# Respeaker_Microphone_Array_v1_0.net
KiCad netlist of a schematic drawn in EAGLE
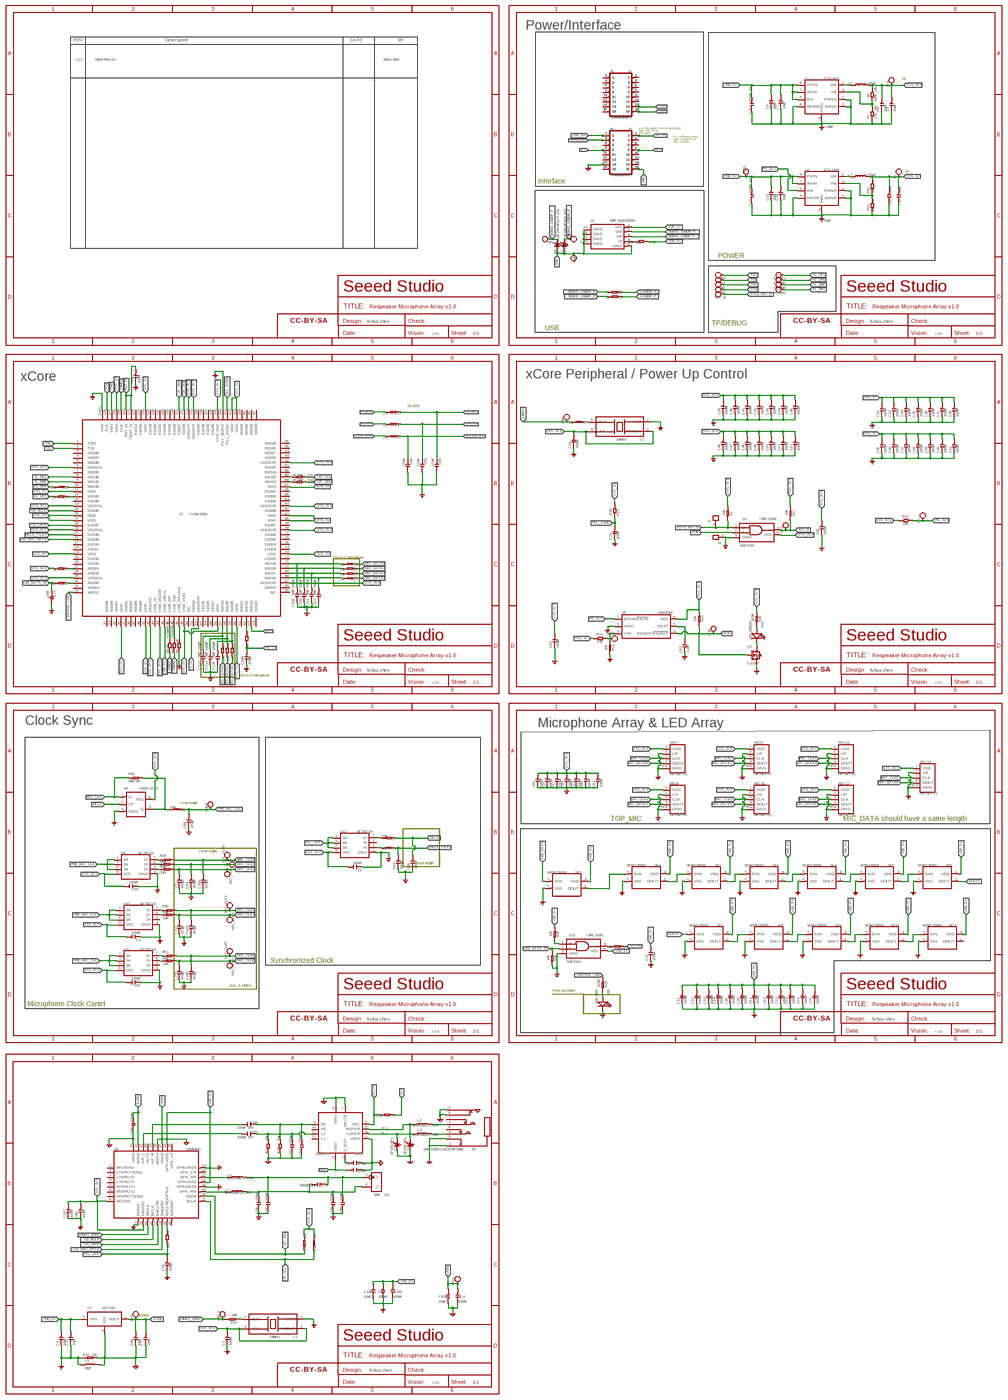
[diagram p0: schematic, sheet 1, overview]
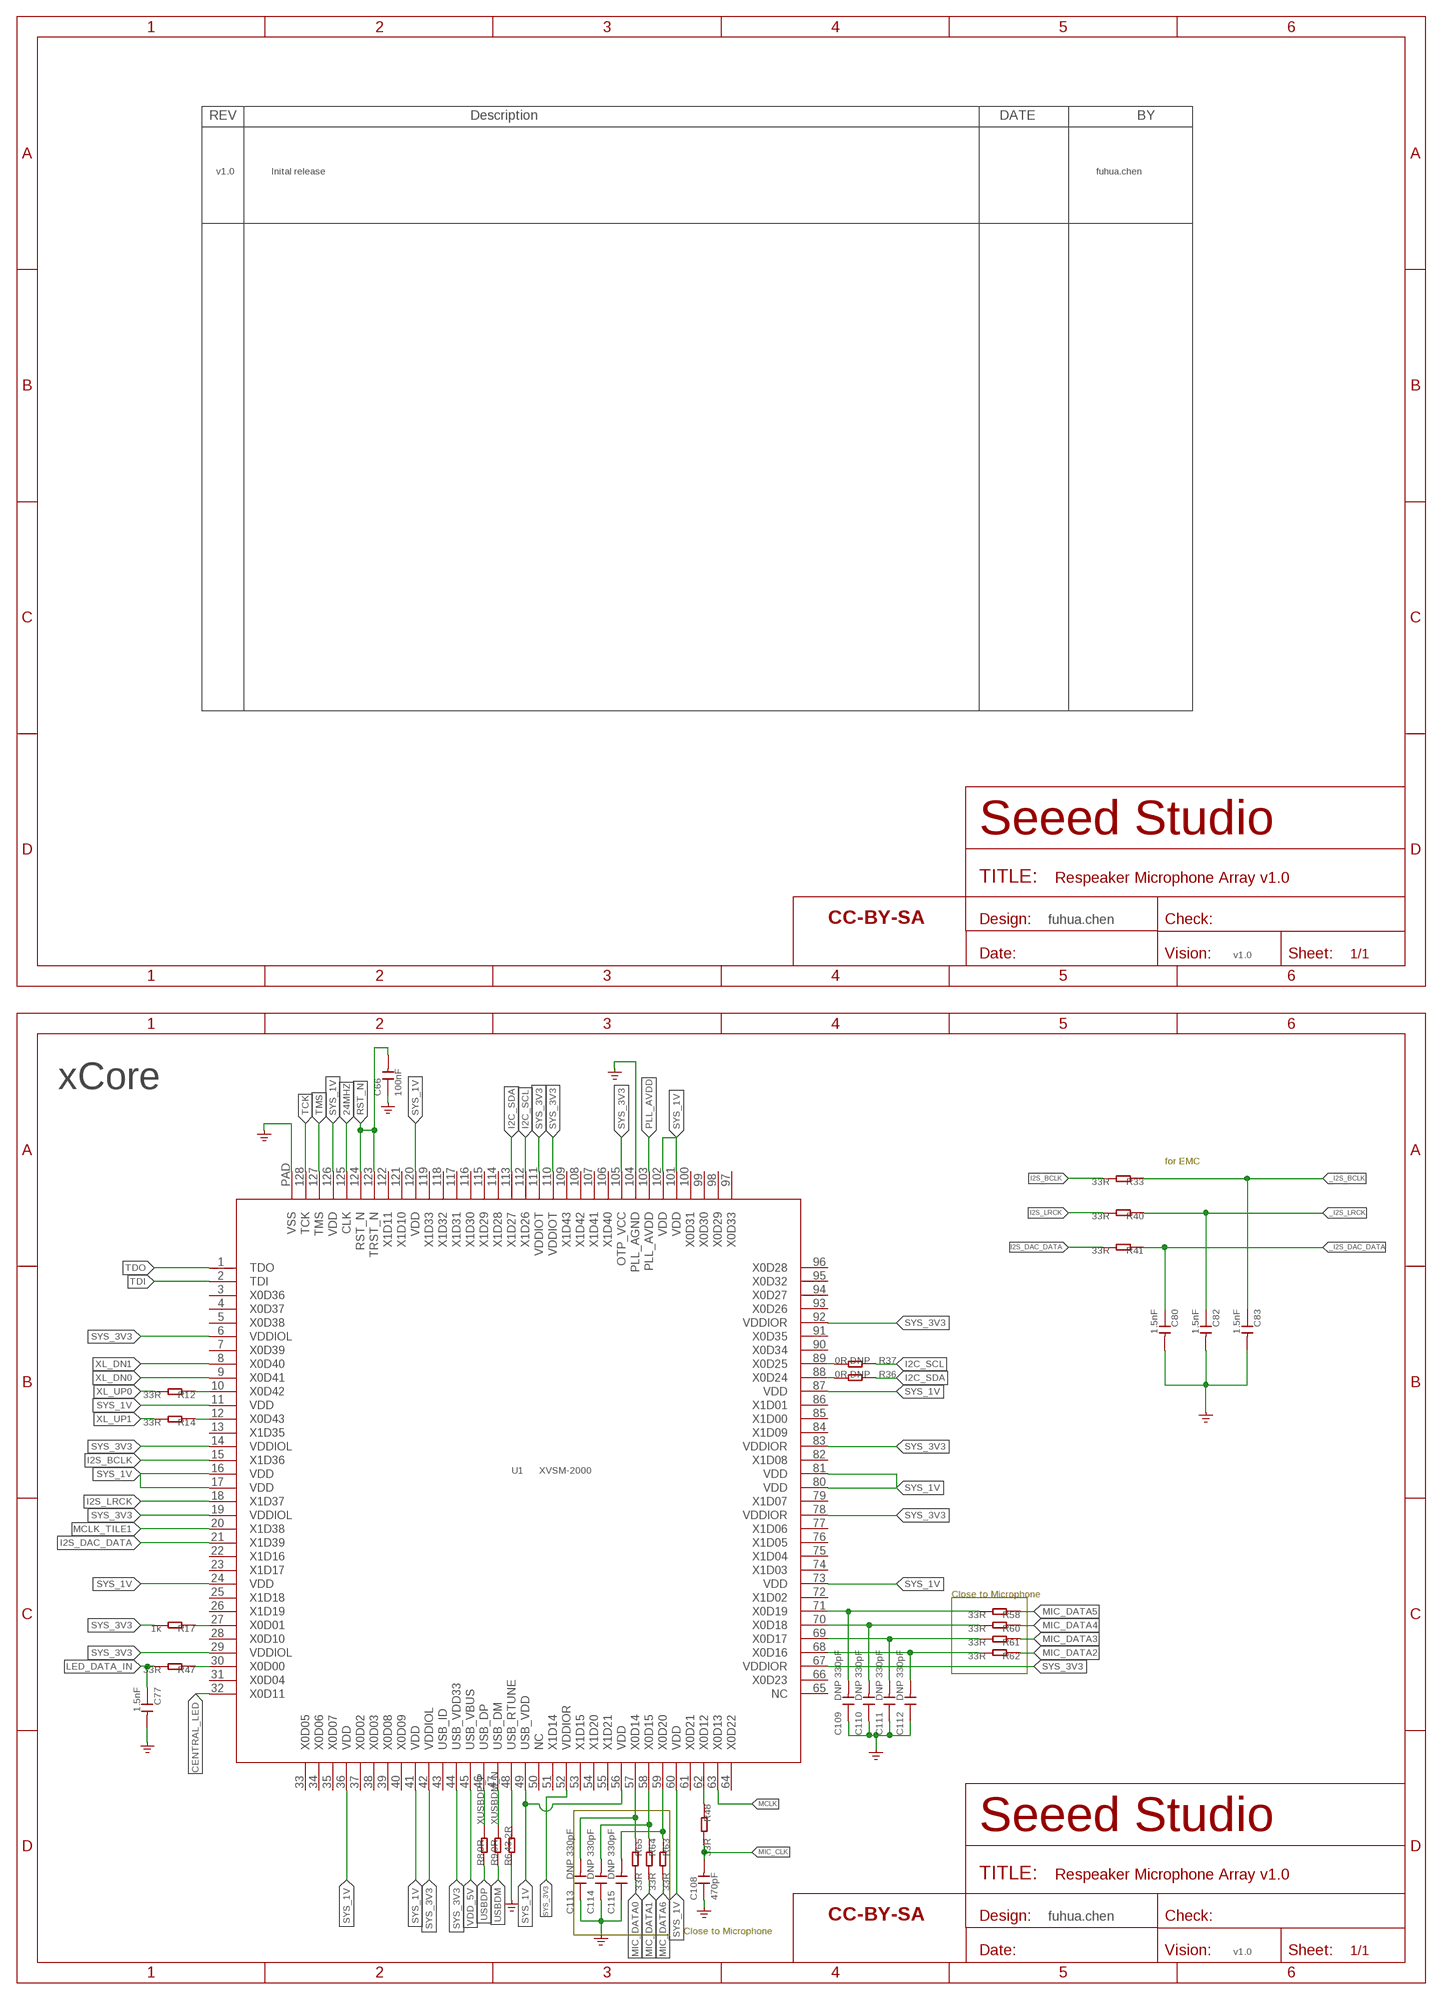
[diagram p1: schematic, sheet 1, part 1 of 4]
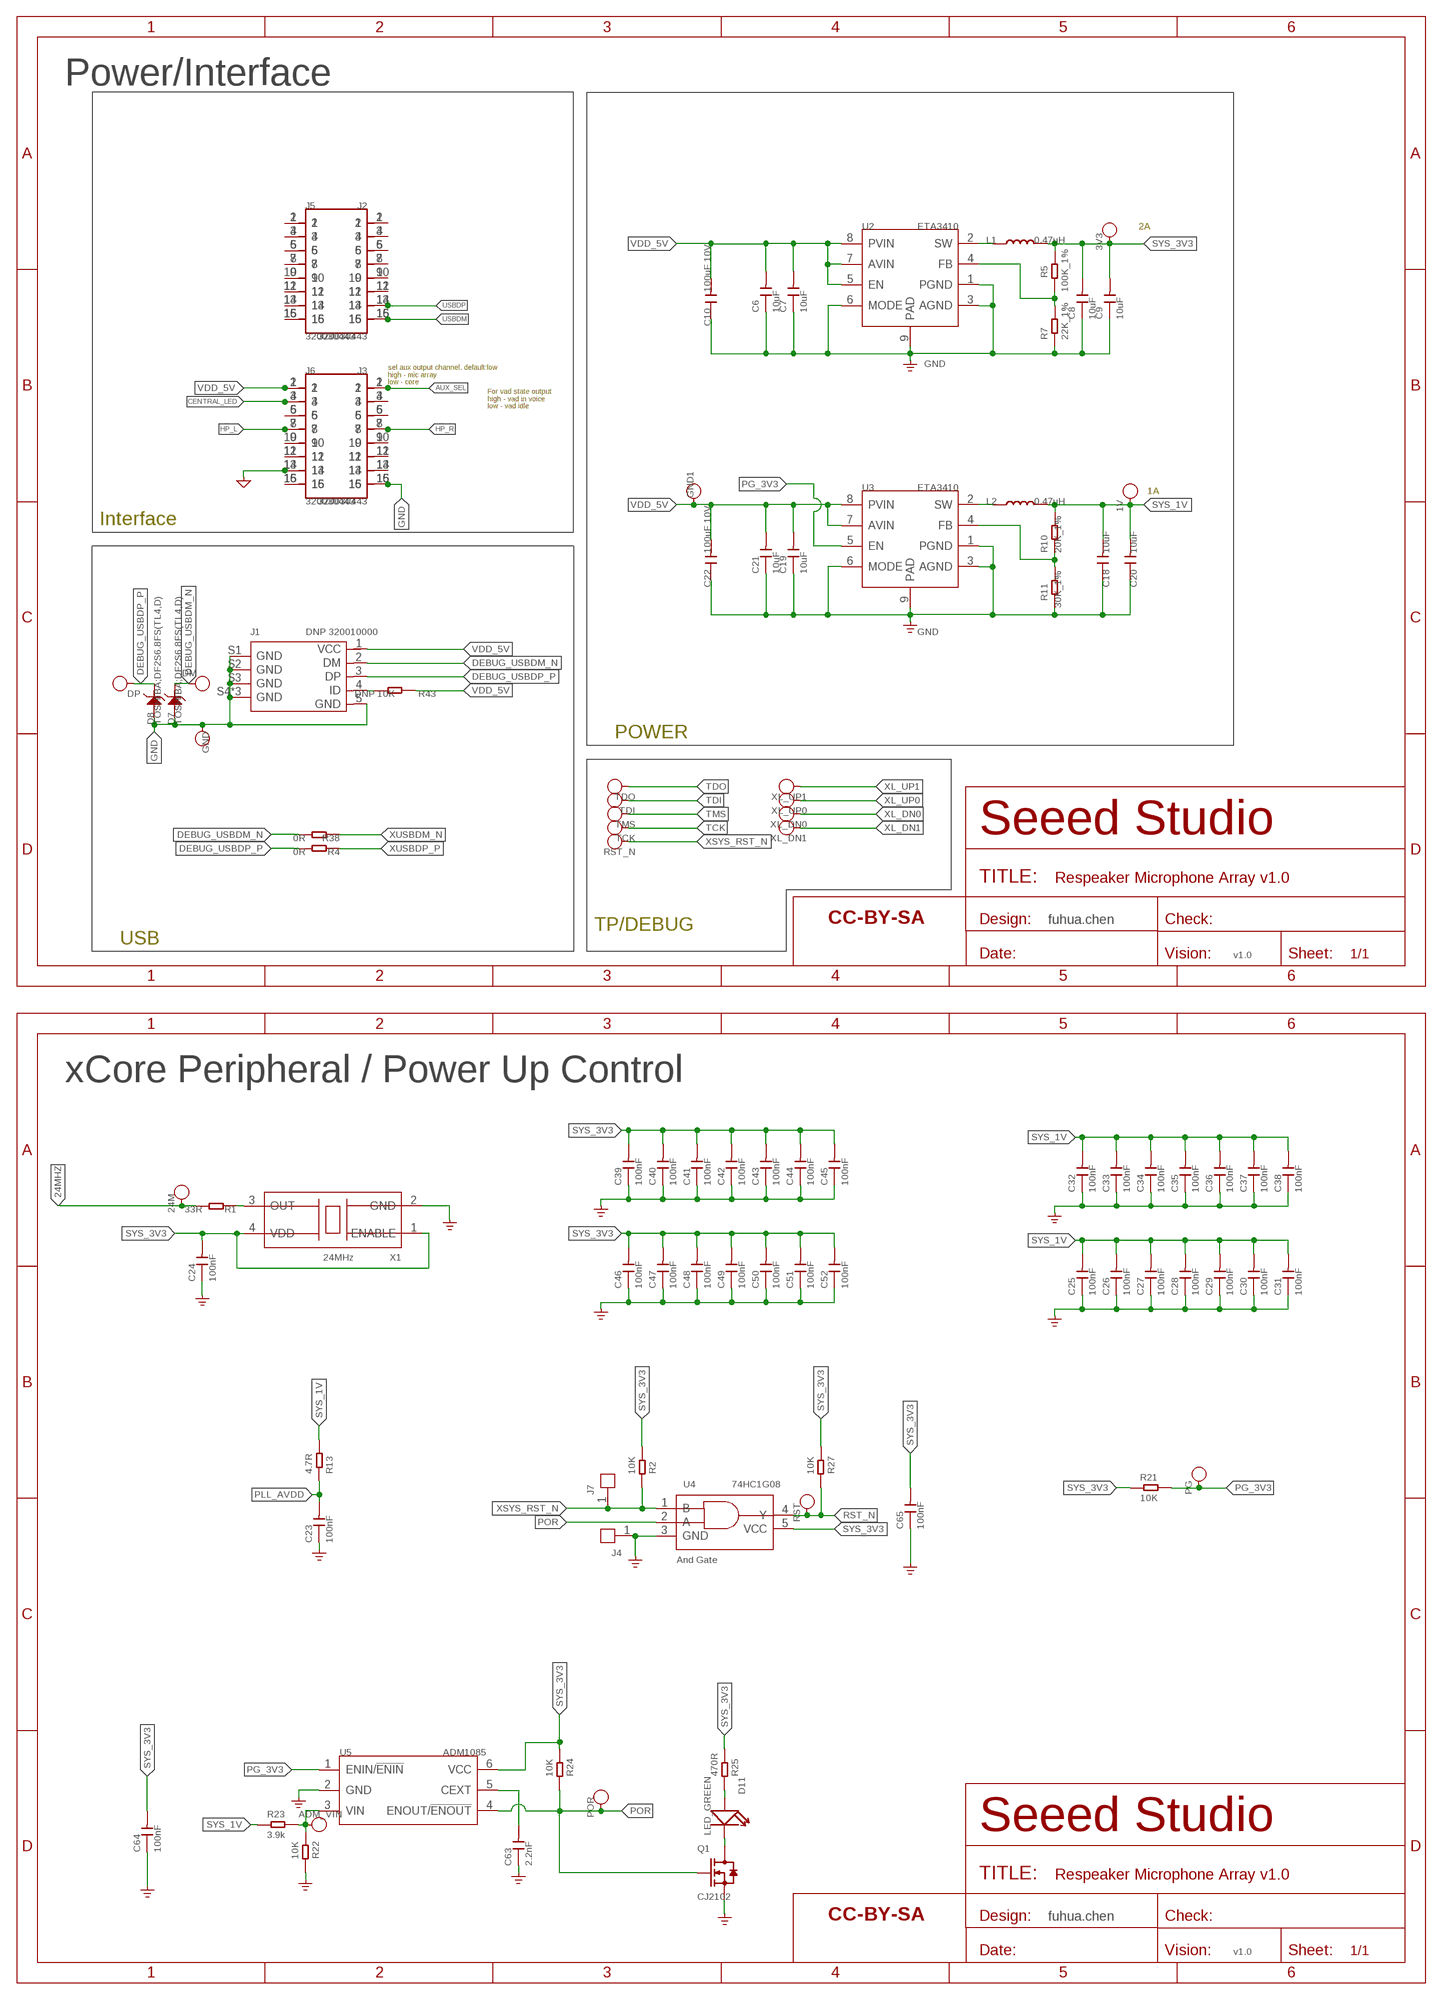
[diagram p2: schematic, sheet 1, part 2 of 4]
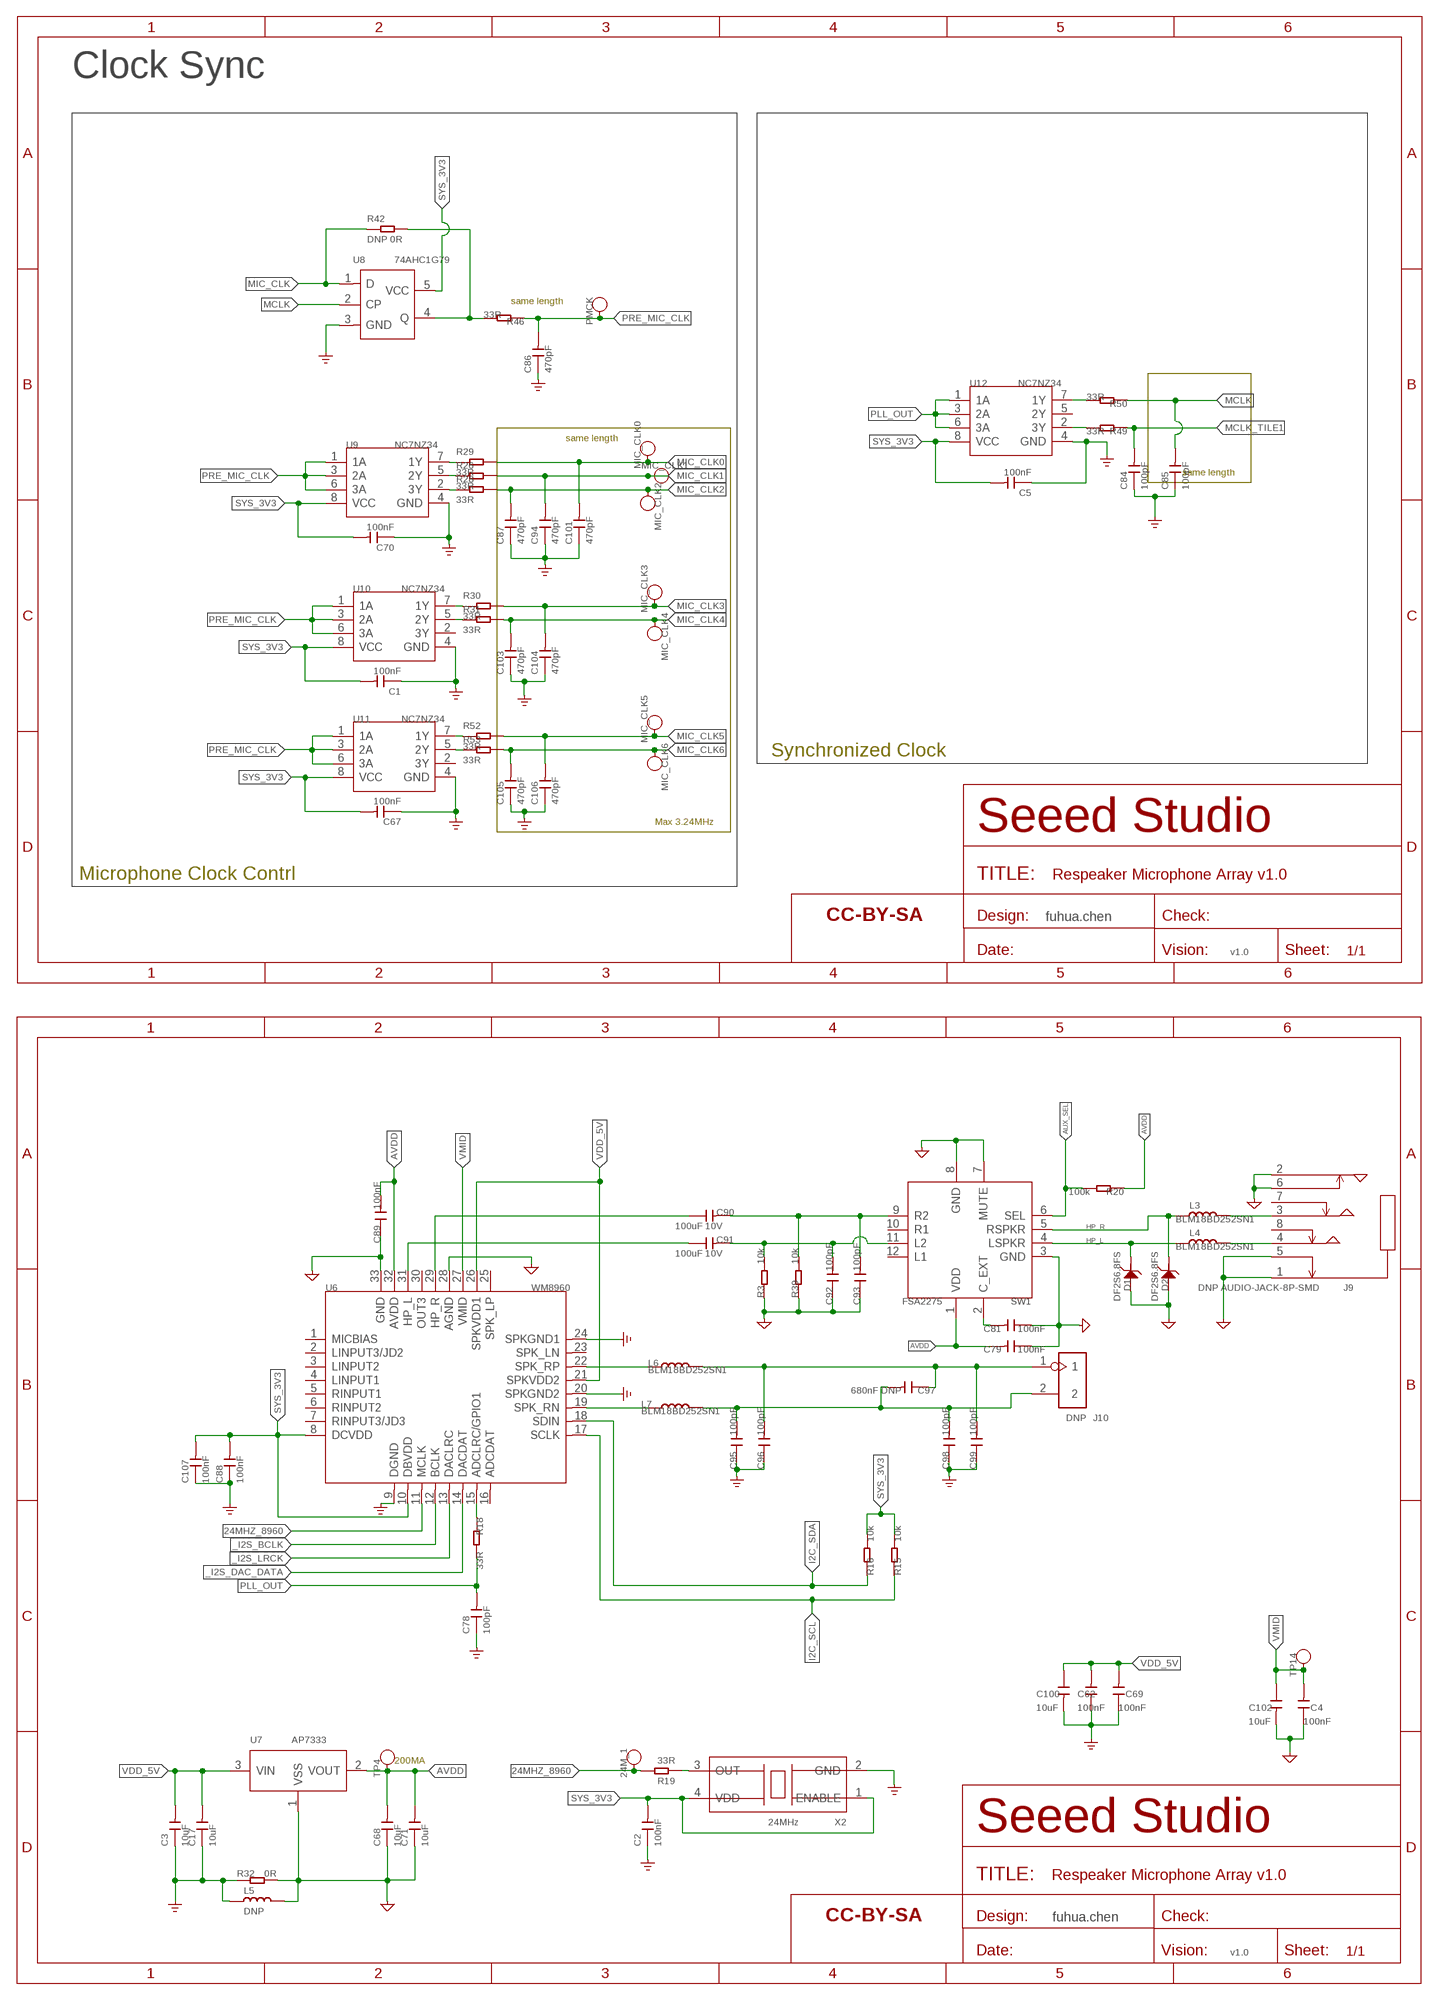
[diagram p3: schematic, sheet 1, part 3 of 4]
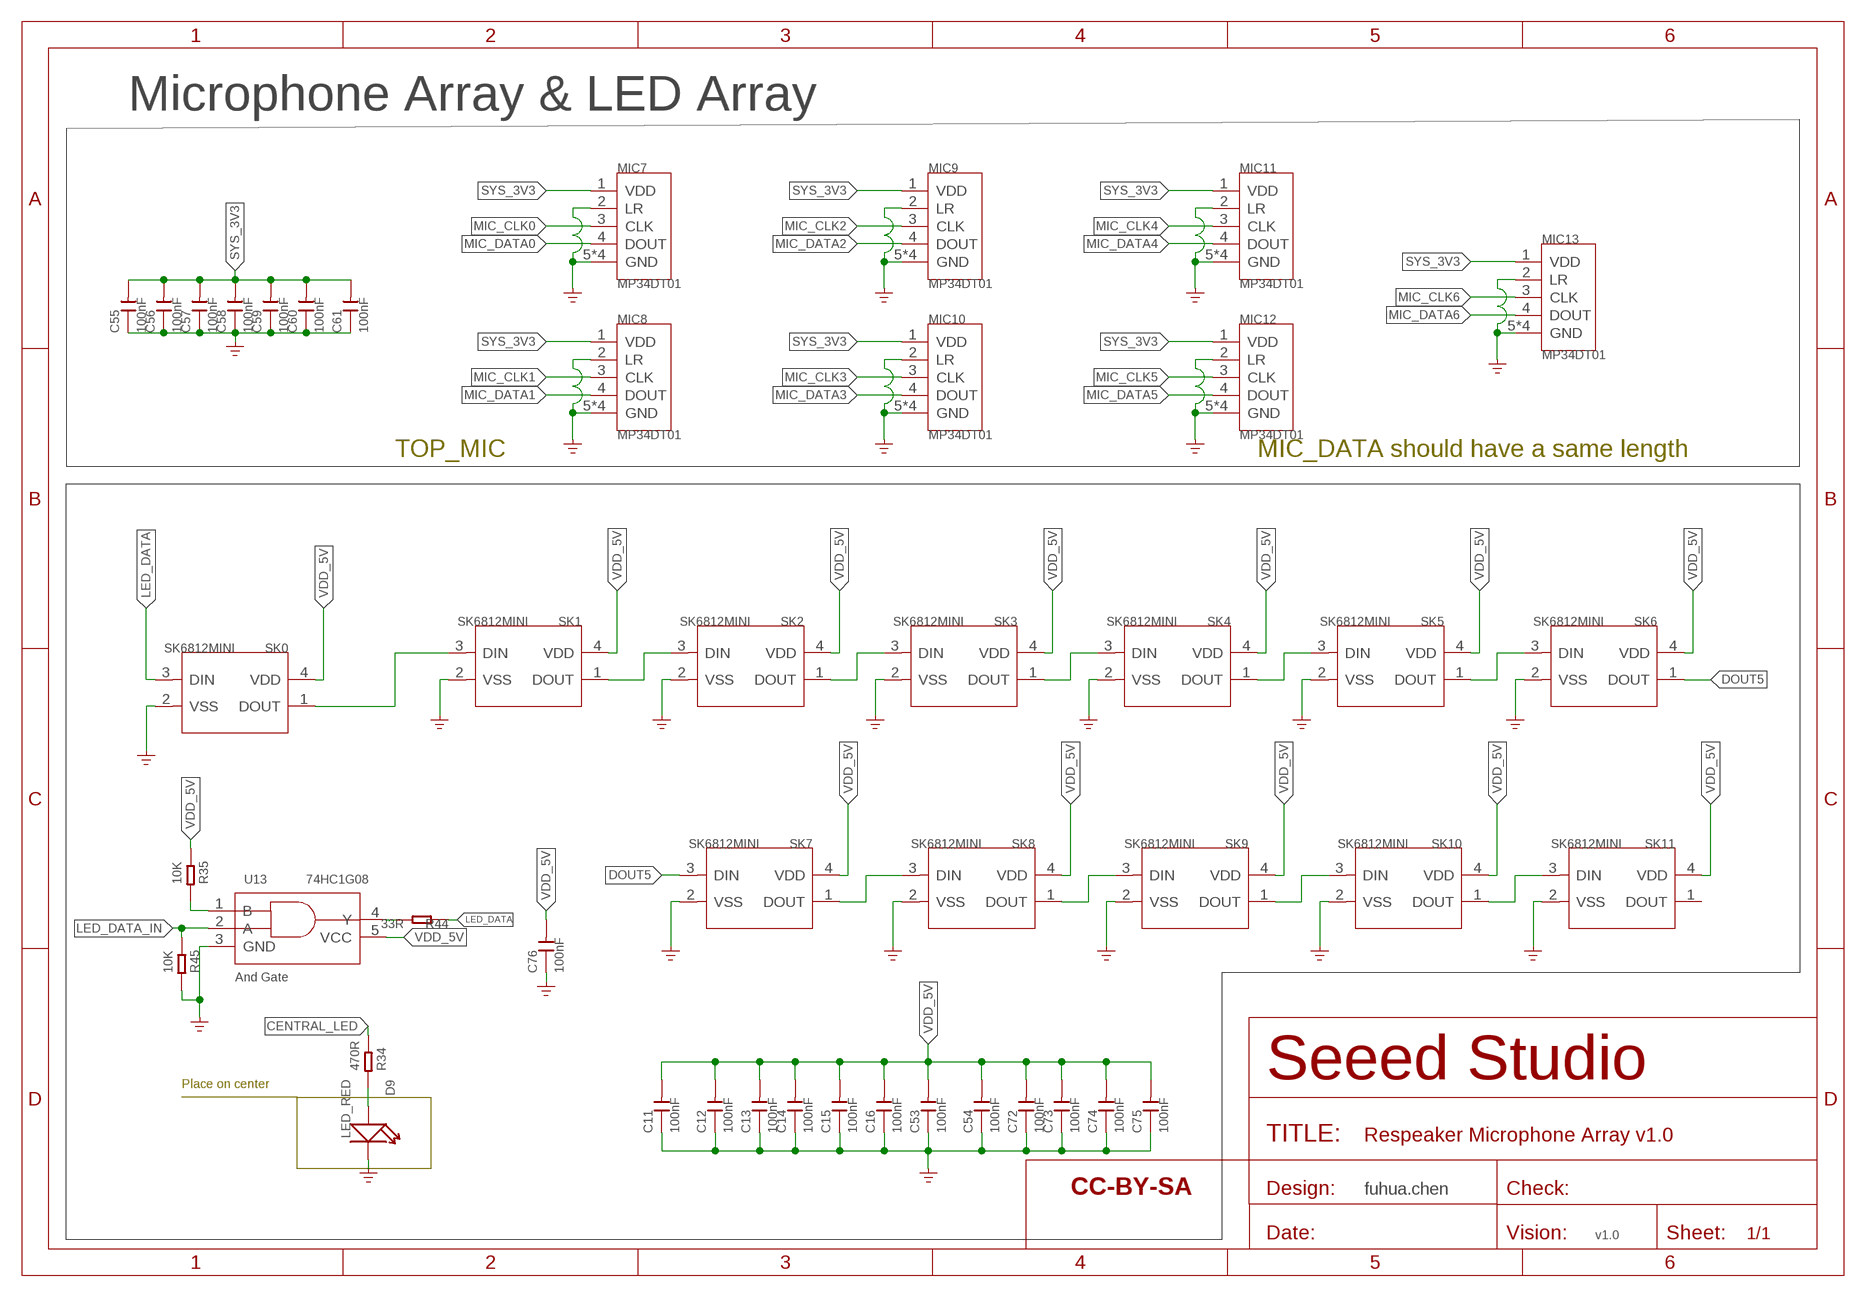
[diagram p4: schematic, sheet 1, part 4 of 4]

(export (version "E")
  (design (tool "Eeschema 10.0.6"))
  (components
    (comp (ref "1V")
      (value "TEST-POINT'4545'")
      (footprint "eagle-import:TP-D45MIL")
      (fields (field (name "PARTNO") "DNP"))
      (libsource (lib "eagle-import") (part "TEST-POINT'4545'"))
    )
    (comp (ref "3V3")
      (value "TEST-POINT'4545'")
      (footprint "eagle-import:TP-D45MIL")
      (fields (field (name "PARTNO") "DNP"))
      (libsource (lib "eagle-import") (part "TEST-POINT'4545'"))
    )
    (comp (ref "24M")
      (value "TEST-POINT'4545'")
      (footprint "eagle-import:TP-D45MIL")
      (fields (field (name "PARTNO") "DNP"))
      (libsource (lib "eagle-import") (part "TEST-POINT'4545'"))
    )
    (comp (ref "24M_1")
      (value "TEST-POINT'4545'")
      (footprint "eagle-import:TP-D45MIL")
      (fields (field (name "PARTNO") "DNP"))
      (libsource (lib "eagle-import") (part "TEST-POINT'4545'"))
    )
    (comp (ref "ADM_VIN")
      (value "TEST-POINT'4545'")
      (footprint "eagle-import:TP-D45MIL")
      (fields (field (name "PARTNO") "DNP"))
      (libsource (lib "eagle-import") (part "TEST-POINT'4545'"))
    )
    (comp (ref "C1")
      (value "100nF")
      (footprint "eagle-import:C0402")
      (libsource (lib "eagle-import") (part "CAP-0402"))
    )
    (comp (ref "C2")
      (value "100nF")
      (footprint "eagle-import:C0402")
      (libsource (lib "eagle-import") (part "CAP-0402"))
    )
    (comp (ref "C3")
      (value "10uF")
      (footprint "eagle-import:C0603")
      (libsource (lib "eagle-import") (part "CAP-0603"))
    )
    (comp (ref "C4")
      (value "100nF")
      (footprint "eagle-import:C0402")
      (libsource (lib "eagle-import") (part "CAP-0402"))
    )
    (comp (ref "C5")
      (value "100nF")
      (footprint "eagle-import:C0402")
      (libsource (lib "eagle-import") (part "CAP-0402"))
    )
    (comp (ref "C6")
      (value "10uF")
      (footprint "eagle-import:C0603")
      (libsource (lib "eagle-import") (part "CAP-0603"))
    )
    (comp (ref "C7")
      (value "10uF")
      (footprint "eagle-import:C0603")
      (libsource (lib "eagle-import") (part "CAP-0603"))
    )
    (comp (ref "C8")
      (value "10uF")
      (footprint "eagle-import:C0603")
      (libsource (lib "eagle-import") (part "CAP-0603"))
    )
    (comp (ref "C9")
      (value "10uF")
      (footprint "eagle-import:C0603")
      (libsource (lib "eagle-import") (part "CAP-0603"))
    )
    (comp (ref "C10")
      (value "100uF 10V")
      (footprint "eagle-import:C1206")
      (libsource (lib "eagle-import") (part "CAP-1206"))
    )
    (comp (ref "C11")
      (value "100nF")
      (footprint "eagle-import:C0402")
      (libsource (lib "eagle-import") (part "CAP-0402"))
    )
    (comp (ref "C12")
      (value "100nF")
      (footprint "eagle-import:C0402")
      (libsource (lib "eagle-import") (part "CAP-0402"))
    )
    (comp (ref "C13")
      (value "100nF")
      (footprint "eagle-import:C0402")
      (libsource (lib "eagle-import") (part "CAP-0402"))
    )
    (comp (ref "C14")
      (value "100nF")
      (footprint "eagle-import:C0402")
      (libsource (lib "eagle-import") (part "CAP-0402"))
    )
    (comp (ref "C15")
      (value "100nF")
      (footprint "eagle-import:C0402")
      (libsource (lib "eagle-import") (part "CAP-0402"))
    )
    (comp (ref "C16")
      (value "100nF")
      (footprint "eagle-import:C0402")
      (libsource (lib "eagle-import") (part "CAP-0402"))
    )
    (comp (ref "C17")
      (value "10uF")
      (footprint "eagle-import:C0603")
      (libsource (lib "eagle-import") (part "CAP-0603"))
    )
    (comp (ref "C18")
      (value "10uF")
      (footprint "eagle-import:C0603")
      (libsource (lib "eagle-import") (part "CAP-0603"))
    )
    (comp (ref "C19")
      (value "10uF")
      (footprint "eagle-import:C0603")
      (libsource (lib "eagle-import") (part "CAP-0603"))
    )
    (comp (ref "C20")
      (value "10uF")
      (footprint "eagle-import:C0603")
      (libsource (lib "eagle-import") (part "CAP-0603"))
    )
    (comp (ref "C21")
      (value "10uF")
      (footprint "eagle-import:C0603")
      (libsource (lib "eagle-import") (part "CAP-0603"))
    )
    (comp (ref "C22")
      (value "100uF 10V")
      (footprint "eagle-import:C1206")
      (libsource (lib "eagle-import") (part "CAP-1206"))
    )
    (comp (ref "C23")
      (value "100nF")
      (footprint "eagle-import:C0402")
      (libsource (lib "eagle-import") (part "CAP-0402"))
    )
    (comp (ref "C24")
      (value "100nF")
      (footprint "eagle-import:C0402")
      (libsource (lib "eagle-import") (part "CAP-0402"))
    )
    (comp (ref "C25")
      (value "100nF")
      (footprint "eagle-import:C0402")
      (libsource (lib "eagle-import") (part "CAP-0402"))
    )
    (comp (ref "C26")
      (value "100nF")
      (footprint "eagle-import:C0402")
      (libsource (lib "eagle-import") (part "CAP-0402"))
    )
    (comp (ref "C27")
      (value "100nF")
      (footprint "eagle-import:C0402")
      (libsource (lib "eagle-import") (part "CAP-0402"))
    )
    (comp (ref "C28")
      (value "100nF")
      (footprint "eagle-import:C0402")
      (libsource (lib "eagle-import") (part "CAP-0402"))
    )
    (comp (ref "C29")
      (value "100nF")
      (footprint "eagle-import:C0402")
      (libsource (lib "eagle-import") (part "CAP-0402"))
    )
    (comp (ref "C30")
      (value "100nF")
      (footprint "eagle-import:C0402")
      (libsource (lib "eagle-import") (part "CAP-0402"))
    )
    (comp (ref "C31")
      (value "100nF")
      (footprint "eagle-import:C0402")
      (libsource (lib "eagle-import") (part "CAP-0402"))
    )
    (comp (ref "C32")
      (value "100nF")
      (footprint "eagle-import:C0402")
      (libsource (lib "eagle-import") (part "CAP-0402"))
    )
    (comp (ref "C33")
      (value "100nF")
      (footprint "eagle-import:C0402")
      (libsource (lib "eagle-import") (part "CAP-0402"))
    )
    (comp (ref "C34")
      (value "100nF")
      (footprint "eagle-import:C0402")
      (libsource (lib "eagle-import") (part "CAP-0402"))
    )
    (comp (ref "C35")
      (value "100nF")
      (footprint "eagle-import:C0402")
      (libsource (lib "eagle-import") (part "CAP-0402"))
    )
    (comp (ref "C36")
      (value "100nF")
      (footprint "eagle-import:C0402")
      (libsource (lib "eagle-import") (part "CAP-0402"))
    )
    (comp (ref "C37")
      (value "100nF")
      (footprint "eagle-import:C0402")
      (libsource (lib "eagle-import") (part "CAP-0402"))
    )
    (comp (ref "C38")
      (value "100nF")
      (footprint "eagle-import:C0402")
      (libsource (lib "eagle-import") (part "CAP-0402"))
    )
    (comp (ref "C39")
      (value "100nF")
      (footprint "eagle-import:C0402")
      (libsource (lib "eagle-import") (part "CAP-0402"))
    )
    (comp (ref "C40")
      (value "100nF")
      (footprint "eagle-import:C0402")
      (libsource (lib "eagle-import") (part "CAP-0402"))
    )
    (comp (ref "C41")
      (value "100nF")
      (footprint "eagle-import:C0402")
      (libsource (lib "eagle-import") (part "CAP-0402"))
    )
    (comp (ref "C42")
      (value "100nF")
      (footprint "eagle-import:C0402")
      (libsource (lib "eagle-import") (part "CAP-0402"))
    )
    (comp (ref "C43")
      (value "100nF")
      (footprint "eagle-import:C0402")
      (libsource (lib "eagle-import") (part "CAP-0402"))
    )
    (comp (ref "C44")
      (value "100nF")
      (footprint "eagle-import:C0402")
      (libsource (lib "eagle-import") (part "CAP-0402"))
    )
    (comp (ref "C45")
      (value "100nF")
      (footprint "eagle-import:C0402")
      (libsource (lib "eagle-import") (part "CAP-0402"))
    )
    (comp (ref "C46")
      (value "100nF")
      (footprint "eagle-import:C0402")
      (libsource (lib "eagle-import") (part "CAP-0402"))
    )
    (comp (ref "C47")
      (value "100nF")
      (footprint "eagle-import:C0402")
      (libsource (lib "eagle-import") (part "CAP-0402"))
    )
    (comp (ref "C48")
      (value "100nF")
      (footprint "eagle-import:C0402")
      (libsource (lib "eagle-import") (part "CAP-0402"))
    )
    (comp (ref "C49")
      (value "100nF")
      (footprint "eagle-import:C0402")
      (libsource (lib "eagle-import") (part "CAP-0402"))
    )
    (comp (ref "C50")
      (value "100nF")
      (footprint "eagle-import:C0402")
      (libsource (lib "eagle-import") (part "CAP-0402"))
    )
    (comp (ref "C51")
      (value "100nF")
      (footprint "eagle-import:C0402")
      (libsource (lib "eagle-import") (part "CAP-0402"))
    )
    (comp (ref "C52")
      (value "100nF")
      (footprint "eagle-import:C0402")
      (libsource (lib "eagle-import") (part "CAP-0402"))
    )
    (comp (ref "C53")
      (value "100nF")
      (footprint "eagle-import:C0402")
      (libsource (lib "eagle-import") (part "CAP-0402"))
    )
    (comp (ref "C54")
      (value "100nF")
      (footprint "eagle-import:C0402")
      (libsource (lib "eagle-import") (part "CAP-0402"))
    )
    (comp (ref "C55")
      (value "100nF")
      (footprint "eagle-import:C0402")
      (libsource (lib "eagle-import") (part "CAP-0402"))
    )
    (comp (ref "C56")
      (value "100nF")
      (footprint "eagle-import:C0402")
      (libsource (lib "eagle-import") (part "CAP-0402"))
    )
    (comp (ref "C57")
      (value "100nF")
      (footprint "eagle-import:C0402")
      (libsource (lib "eagle-import") (part "CAP-0402"))
    )
    (comp (ref "C58")
      (value "100nF")
      (footprint "eagle-import:C0402")
      (libsource (lib "eagle-import") (part "CAP-0402"))
    )
    (comp (ref "C59")
      (value "100nF")
      (footprint "eagle-import:C0402")
      (libsource (lib "eagle-import") (part "CAP-0402"))
    )
    (comp (ref "C60")
      (value "100nF")
      (footprint "eagle-import:C0402")
      (libsource (lib "eagle-import") (part "CAP-0402"))
    )
    (comp (ref "C61")
      (value "100nF")
      (footprint "eagle-import:C0402")
      (libsource (lib "eagle-import") (part "CAP-0402"))
    )
    (comp (ref "C62")
      (value "100nF")
      (footprint "eagle-import:C0402")
      (libsource (lib "eagle-import") (part "CAP-0402"))
    )
    (comp (ref "C63")
      (value "2.2nF")
      (footprint "eagle-import:C0402")
      (libsource (lib "eagle-import") (part "CAP-0402"))
    )
    (comp (ref "C64")
      (value "100nF")
      (footprint "eagle-import:C0402")
      (libsource (lib "eagle-import") (part "CAP-0402"))
    )
    (comp (ref "C65")
      (value "100nF")
      (footprint "eagle-import:C0402")
      (libsource (lib "eagle-import") (part "CAP-0402"))
    )
    (comp (ref "C66")
      (value "100nF")
      (footprint "eagle-import:C0402")
      (libsource (lib "eagle-import") (part "CAP-0402"))
    )
    (comp (ref "C67")
      (value "100nF")
      (footprint "eagle-import:C0402")
      (libsource (lib "eagle-import") (part "CAP-0402"))
    )
    (comp (ref "C68")
      (value "10uF")
      (footprint "eagle-import:C0603")
      (libsource (lib "eagle-import") (part "CAP-0603"))
    )
    (comp (ref "C69")
      (value "100nF")
      (footprint "eagle-import:C0402")
      (libsource (lib "eagle-import") (part "CAP-0402"))
    )
    (comp (ref "C70")
      (value "100nF")
      (footprint "eagle-import:C0402")
      (libsource (lib "eagle-import") (part "CAP-0402"))
    )
    (comp (ref "C71")
      (value "10uF")
      (footprint "eagle-import:C0603")
      (libsource (lib "eagle-import") (part "CAP-0603"))
    )
    (comp (ref "C72")
      (value "100nF")
      (footprint "eagle-import:C0402")
      (libsource (lib "eagle-import") (part "CAP-0402"))
    )
    (comp (ref "C73")
      (value "100nF")
      (footprint "eagle-import:C0402")
      (libsource (lib "eagle-import") (part "CAP-0402"))
    )
    (comp (ref "C74")
      (value "100nF")
      (footprint "eagle-import:C0402")
      (libsource (lib "eagle-import") (part "CAP-0402"))
    )
    (comp (ref "C75")
      (value "100nF")
      (footprint "eagle-import:C0402")
      (libsource (lib "eagle-import") (part "CAP-0402"))
    )
    (comp (ref "C76")
      (value "100nF")
      (footprint "eagle-import:C0402")
      (libsource (lib "eagle-import") (part "CAP-0402"))
    )
    (comp (ref "C77")
      (value "1.5nF")
      (footprint "eagle-import:C0402")
      (libsource (lib "eagle-import") (part "CAP-0402"))
    )
    (comp (ref "C78")
      (value "100pF")
      (footprint "eagle-import:C0402")
      (libsource (lib "eagle-import") (part "CAP-0402"))
    )
    (comp (ref "C79")
      (value "100nF")
      (footprint "eagle-import:C0402")
      (libsource (lib "eagle-import") (part "CAP-0402"))
    )
    (comp (ref "C80")
      (value "1.5nF")
      (footprint "eagle-import:C0402")
      (libsource (lib "eagle-import") (part "CAP-0402"))
    )
    (comp (ref "C81")
      (value "100nF")
      (footprint "eagle-import:C0402")
      (libsource (lib "eagle-import") (part "CAP-0402"))
    )
    (comp (ref "C82")
      (value "1.5nF")
      (footprint "eagle-import:C0402")
      (libsource (lib "eagle-import") (part "CAP-0402"))
    )
    (comp (ref "C83")
      (value "1.5nF")
      (footprint "eagle-import:C0402")
      (libsource (lib "eagle-import") (part "CAP-0402"))
    )
    (comp (ref "C84")
      (value "100pF")
      (footprint "eagle-import:C0402")
      (libsource (lib "eagle-import") (part "CAP-0402"))
    )
    (comp (ref "C85")
      (value "100pF")
      (footprint "eagle-import:C0402")
      (libsource (lib "eagle-import") (part "CAP-0402"))
    )
    (comp (ref "C86")
      (value "470pF")
      (footprint "eagle-import:C0402")
      (libsource (lib "eagle-import") (part "CAP-0402"))
    )
    (comp (ref "C87")
      (value "470pF")
      (footprint "eagle-import:C0402")
      (libsource (lib "eagle-import") (part "CAP-0402"))
    )
    (comp (ref "C88")
      (value "100nF")
      (footprint "eagle-import:C0402")
      (libsource (lib "eagle-import") (part "CAP-0402"))
    )
    (comp (ref "C89")
      (value "100nF")
      (footprint "eagle-import:C0402")
      (libsource (lib "eagle-import") (part "CAP-0402"))
    )
    (comp (ref "C90")
      (value "100uF 10V")
      (footprint "eagle-import:C1206")
      (libsource (lib "eagle-import") (part "CAP-1206"))
    )
    (comp (ref "C91")
      (value "100uF 10V")
      (footprint "eagle-import:C1206")
      (libsource (lib "eagle-import") (part "CAP-1206"))
    )
    (comp (ref "C92")
      (value "100pF")
      (footprint "eagle-import:C0402")
      (libsource (lib "eagle-import") (part "CAP-0402"))
    )
    (comp (ref "C93")
      (value "100pF")
      (footprint "eagle-import:C0402")
      (libsource (lib "eagle-import") (part "CAP-0402"))
    )
    (comp (ref "C94")
      (value "470pF")
      (footprint "eagle-import:C0402")
      (libsource (lib "eagle-import") (part "CAP-0402"))
    )
    (comp (ref "C95")
      (value "100pF")
      (footprint "eagle-import:C0402")
      (libsource (lib "eagle-import") (part "CAP-0402"))
    )
    (comp (ref "C96")
      (value "100pF")
      (footprint "eagle-import:C0402")
      (libsource (lib "eagle-import") (part "CAP-0402"))
    )
    (comp (ref "C97")
      (value "680nF DNP")
      (footprint "eagle-import:C0402")
      (libsource (lib "eagle-import") (part "CAP-0402"))
    )
    (comp (ref "C98")
      (value "100pF")
      (footprint "eagle-import:C0402")
      (libsource (lib "eagle-import") (part "CAP-0402"))
    )
    (comp (ref "C99")
      (value "100pF")
      (footprint "eagle-import:C0402")
      (libsource (lib "eagle-import") (part "CAP-0402"))
    )
    (comp (ref "C100")
      (value "10uF")
      (footprint "eagle-import:C0603")
      (libsource (lib "eagle-import") (part "CAP-0603"))
    )
    (comp (ref "C101")
      (value "470pF")
      (footprint "eagle-import:C0402")
      (libsource (lib "eagle-import") (part "CAP-0402"))
    )
    (comp (ref "C102")
      (value "10uF")
      (footprint "eagle-import:C0603")
      (libsource (lib "eagle-import") (part "CAP-0603"))
    )
    (comp (ref "C103")
      (value "470pF")
      (footprint "eagle-import:C0402")
      (libsource (lib "eagle-import") (part "CAP-0402"))
    )
    (comp (ref "C104")
      (value "470pF")
      (footprint "eagle-import:C0402")
      (libsource (lib "eagle-import") (part "CAP-0402"))
    )
    (comp (ref "C105")
      (value "470pF")
      (footprint "eagle-import:C0402")
      (libsource (lib "eagle-import") (part "CAP-0402"))
    )
    (comp (ref "C106")
      (value "470pF")
      (footprint "eagle-import:C0402")
      (libsource (lib "eagle-import") (part "CAP-0402"))
    )
    (comp (ref "C107")
      (value "100nF")
      (footprint "eagle-import:C0402")
      (libsource (lib "eagle-import") (part "CAP-0402"))
    )
    (comp (ref "C108")
      (value "470pF")
      (footprint "eagle-import:C0402")
      (libsource (lib "eagle-import") (part "CAP-0402"))
    )
    (comp (ref "C109")
      (value "DNP 330pF")
      (footprint "eagle-import:C0402")
      (libsource (lib "eagle-import") (part "CAP-0402"))
    )
    (comp (ref "C110")
      (value "DNP 330pF")
      (footprint "eagle-import:C0402")
      (libsource (lib "eagle-import") (part "CAP-0402"))
    )
    (comp (ref "C111")
      (value "DNP 330pF")
      (footprint "eagle-import:C0402")
      (libsource (lib "eagle-import") (part "CAP-0402"))
    )
    (comp (ref "C112")
      (value "DNP 330pF")
      (footprint "eagle-import:C0402")
      (libsource (lib "eagle-import") (part "CAP-0402"))
    )
    (comp (ref "C113")
      (value "DNP 330pF")
      (footprint "eagle-import:C0402")
      (libsource (lib "eagle-import") (part "CAP-0402"))
    )
    (comp (ref "C114")
      (value "DNP 330pF")
      (footprint "eagle-import:C0402")
      (libsource (lib "eagle-import") (part "CAP-0402"))
    )
    (comp (ref "C115")
      (value "DNP 330pF")
      (footprint "eagle-import:C0402")
      (libsource (lib "eagle-import") (part "CAP-0402"))
    )
    (comp (ref "D1")
      (value "DF2S6.8FS")
      (footprint "eagle-import:SOD-923")
      (libsource (lib "eagle-import") (part "D-ESD-2P'DF2S6.8FS'"))
    )
    (comp (ref "D2")
      (value "DF2S6.8FS")
      (footprint "eagle-import:SOD-923")
      (libsource (lib "eagle-import") (part "D-ESD-2P'DF2S6.8FS'"))
    )
    (comp (ref "D7")
      (value "TOSHIBA;DF2S6.8FS(TL4,D)")
      (footprint "eagle-import:SOD-923")
      (libsource (lib "eagle-import") (part "D-ESD-2P'DF2S6.8FS'"))
    )
    (comp (ref "D8")
      (value "TOSHIBA;DF2S6.8FS(TL4,D)")
      (footprint "eagle-import:SOD-923")
      (libsource (lib "eagle-import") (part "D-ESD-2P'DF2S6.8FS'"))
    )
    (comp (ref "D9")
      (value "LED_RED")
      (footprint "eagle-import:LED-0402")
      (libsource (lib "eagle-import") (part "LED-0402"))
    )
    (comp (ref "D11")
      (value "LED_GREEN")
      (footprint "eagle-import:LED-0402")
      (libsource (lib "eagle-import") (part "LED-0402"))
    )
    (comp (ref "DM")
      (value "TEST-POINT'4545'")
      (footprint "eagle-import:TP-D45MIL")
      (fields (field (name "PARTNO") "DNP"))
      (libsource (lib "eagle-import") (part "TEST-POINT'4545'"))
    )
    (comp (ref "DP")
      (value "TEST-POINT'4545'")
      (footprint "eagle-import:TP-D45MIL")
      (fields (field (name "PARTNO") "DNP"))
      (libsource (lib "eagle-import") (part "TEST-POINT'4545'"))
    )
    (comp (ref "FR1")
      (value "SEEEDSTUDIO-OPEN-SCH-FRAME")
      (footprint "eagle-import:SEEEDSTUDIO-PCB-FRAME")
      (libsource (lib "eagle-import") (part "SEEEDSTUDIO-OPEN-SCH-FRAME"))
    )
    (comp (ref "FR2")
      (value "SEEEDSTUDIO-OPEN-SCH-FRAME")
      (footprint "eagle-import:SEEEDSTUDIO-PCB-FRAME")
      (libsource (lib "eagle-import") (part "SEEEDSTUDIO-OPEN-SCH-FRAME"))
    )
    (comp (ref "FR3")
      (value "SEEEDSTUDIO-OPEN-SCH-FRAME")
      (footprint "eagle-import:SEEEDSTUDIO-PCB-FRAME")
      (libsource (lib "eagle-import") (part "SEEEDSTUDIO-OPEN-SCH-FRAME"))
    )
    (comp (ref "FR4")
      (value "SEEEDSTUDIO-OPEN-SCH-FRAME")
      (footprint "eagle-import:SEEEDSTUDIO-PCB-FRAME")
      (libsource (lib "eagle-import") (part "SEEEDSTUDIO-OPEN-SCH-FRAME"))
    )
    (comp (ref "FR5")
      (value "SEEEDSTUDIO-OPEN-SCH-FRAME")
      (footprint "eagle-import:SEEEDSTUDIO-PCB-FRAME")
      (libsource (lib "eagle-import") (part "SEEEDSTUDIO-OPEN-SCH-FRAME"))
    )
    (comp (ref "FR7")
      (value "SEEEDSTUDIO-OPEN-SCH-FRAME")
      (footprint "eagle-import:SEEEDSTUDIO-PCB-FRAME")
      (libsource (lib "eagle-import") (part "SEEEDSTUDIO-OPEN-SCH-FRAME"))
    )
    (comp (ref "FR8")
      (value "SEEEDSTUDIO-OPEN-SCH-FRAME")
      (footprint "eagle-import:SEEEDSTUDIO-PCB-FRAME")
      (libsource (lib "eagle-import") (part "SEEEDSTUDIO-OPEN-SCH-FRAME"))
    )
    (comp (ref "GND")
      (value "TEST-POINT'4545'")
      (footprint "eagle-import:TP-D45MIL")
      (fields (field (name "PARTNO") "DNP"))
      (libsource (lib "eagle-import") (part "TEST-POINT'4545'"))
    )
    (comp (ref "GND1")
      (value "TEST-POINT'4545'")
      (footprint "eagle-import:TP-D45MIL")
      (fields (field (name "PARTNO") "DNP"))
      (libsource (lib "eagle-import") (part "TEST-POINT'4545'"))
    )
    (comp (ref "J1")
      (value "DNP 320010000")
      (footprint "eagle-import:MICRO-USB5+4P-SMD-0.65-B")
      (libsource (lib "eagle-import") (part "MICRO-USB5+4P'5+4P'"))
    )
    (comp (ref "J2")
      (value "320030443")
      (footprint "eagle-import:H2X8-SMD-2.0")
      (libsource (lib "eagle-import") (part "HEADER-2X8P-SMD-2.0"))
    )
    (comp (ref "J3")
      (value "320030443")
      (footprint "eagle-import:H2X8-SMD-2.0")
      (libsource (lib "eagle-import") (part "HEADER-2X8P-SMD-2.0"))
    )
    (comp (ref "J4")
      (value "HEADER-1P'20'")
      (footprint "eagle-import:1P-40_25MIL")
      (libsource (lib "eagle-import") (part "HEADER-1P'20'"))
    )
    (comp (ref "J5")
      (value "320030443")
      (footprint "eagle-import:H2X8-SMD-2.0")
      (libsource (lib "eagle-import") (part "HEADER-2X8P-SMD-2.0"))
    )
    (comp (ref "J6")
      (value "320030443")
      (footprint "eagle-import:H2X8-SMD-2.0")
      (libsource (lib "eagle-import") (part "HEADER-2X8P-SMD-2.0"))
    )
    (comp (ref "J7")
      (value "HEADER-1P'20'")
      (footprint "eagle-import:1P-40_25MIL")
      (libsource (lib "eagle-import") (part "HEADER-1P'20'"))
    )
    (comp (ref "J9")
      (value "DNP AUDIO-JACK-8P-SMD")
      (footprint "eagle-import:AUDIO8P-SMD-3.5-14.5X6.1X4.0MM")
      (libsource (lib "eagle-import") (part "AUDIO-JACK-8P-SMD'PJ-393'"))
    )
    (comp (ref "J10")
      (value "DNP")
      (footprint "eagle-import:H2-2.54")
      (libsource (lib "eagle-import") (part "HEADER-2P-65/35MIL"))
    )
    (comp (ref "L1")
      (value "0.47uH")
      (footprint "eagle-import:L201610")
      (libsource (lib "eagle-import") (part "L-MPM201610SR33_T"))
    )
    (comp (ref "L2")
      (value "0.47uH")
      (footprint "eagle-import:L201610")
      (libsource (lib "eagle-import") (part "L-MPM201610SR33_T"))
    )
    (comp (ref "L3")
      (value "BLM18BD252SN1")
      (footprint "eagle-import:L0603")
      (libsource (lib "eagle-import") (part "INDUCTOR/FERRITE-BEAD'0603'"))
    )
    (comp (ref "L4")
      (value "BLM18BD252SN1")
      (footprint "eagle-import:L0603")
      (libsource (lib "eagle-import") (part "INDUCTOR/FERRITE-BEAD'0603'"))
    )
    (comp (ref "L5")
      (value "DNP")
      (footprint "eagle-import:L0603")
      (libsource (lib "eagle-import") (part "INDUCTOR/FERRITE-BEAD'0603'"))
    )
    (comp (ref "L6")
      (value "BLM18BD252SN1")
      (footprint "eagle-import:L0603")
      (libsource (lib "eagle-import") (part "INDUCTOR/FERRITE-BEAD'0603'"))
    )
    (comp (ref "L7")
      (value "BLM18BD252SN1")
      (footprint "eagle-import:L0603")
      (libsource (lib "eagle-import") (part "INDUCTOR/FERRITE-BEAD'0603'"))
    )
    (comp (ref "MIC7")
      (value "MP34DT01")
      (footprint "eagle-import:HCLGA5P-3X4X1MM")
      (libsource (lib "eagle-import") (part "MICROPHONE-MP34DT01"))
    )
    (comp (ref "MIC8")
      (value "MP34DT01")
      (footprint "eagle-import:HCLGA5P-3X4X1MM")
      (libsource (lib "eagle-import") (part "MICROPHONE-MP34DT01"))
    )
    (comp (ref "MIC9")
      (value "MP34DT01")
      (footprint "eagle-import:HCLGA5P-3X4X1MM")
      (libsource (lib "eagle-import") (part "MICROPHONE-MP34DT01"))
    )
    (comp (ref "MIC10")
      (value "MP34DT01")
      (footprint "eagle-import:HCLGA5P-3X4X1MM")
      (libsource (lib "eagle-import") (part "MICROPHONE-MP34DT01"))
    )
    (comp (ref "MIC11")
      (value "MP34DT01")
      (footprint "eagle-import:HCLGA5P-3X4X1MM")
      (libsource (lib "eagle-import") (part "MICROPHONE-MP34DT01"))
    )
    (comp (ref "MIC12")
      (value "MP34DT01")
      (footprint "eagle-import:HCLGA5P-3X4X1MM")
      (libsource (lib "eagle-import") (part "MICROPHONE-MP34DT01"))
    )
    (comp (ref "MIC13")
      (value "MP34DT01")
      (footprint "eagle-import:HCLGA5P-3X4X1MM")
      (libsource (lib "eagle-import") (part "MICROPHONE-MP34DT01"))
    )
    (comp (ref "MIC_CLK0")
      (value "TEST-POINT'4545'")
      (footprint "eagle-import:TP-D45MIL")
      (fields (field (name "PARTNO") "DNP"))
      (libsource (lib "eagle-import") (part "TEST-POINT'4545'"))
    )
    (comp (ref "MIC_CLK1")
      (value "TEST-POINT'4545'")
      (footprint "eagle-import:TP-D45MIL")
      (fields (field (name "PARTNO") "DNP"))
      (libsource (lib "eagle-import") (part "TEST-POINT'4545'"))
    )
    (comp (ref "MIC_CLK2")
      (value "TEST-POINT'4545'")
      (footprint "eagle-import:TP-D45MIL")
      (fields (field (name "PARTNO") "DNP"))
      (libsource (lib "eagle-import") (part "TEST-POINT'4545'"))
    )
    (comp (ref "MIC_CLK3")
      (value "TEST-POINT'4545'")
      (footprint "eagle-import:TP-D45MIL")
      (fields (field (name "PARTNO") "DNP"))
      (libsource (lib "eagle-import") (part "TEST-POINT'4545'"))
    )
    (comp (ref "MIC_CLK4")
      (value "TEST-POINT'4545'")
      (footprint "eagle-import:TP-D45MIL")
      (fields (field (name "PARTNO") "DNP"))
      (libsource (lib "eagle-import") (part "TEST-POINT'4545'"))
    )
    (comp (ref "MIC_CLK5")
      (value "TEST-POINT'4545'")
      (footprint "eagle-import:TP-D45MIL")
      (fields (field (name "PARTNO") "DNP"))
      (libsource (lib "eagle-import") (part "TEST-POINT'4545'"))
    )
    (comp (ref "MIC_CLK6")
      (value "TEST-POINT'4545'")
      (footprint "eagle-import:TP-D45MIL")
      (fields (field (name "PARTNO") "DNP"))
      (libsource (lib "eagle-import") (part "TEST-POINT'4545'"))
    )
    (comp (ref "PG")
      (value "TEST-POINT'4545'")
      (footprint "eagle-import:TP-D45MIL")
      (fields (field (name "PARTNO") "DNP"))
      (libsource (lib "eagle-import") (part "TEST-POINT'4545'"))
    )
    (comp (ref "PMCK")
      (value "TEST-POINT'4545'")
      (footprint "eagle-import:TP-D45MIL")
      (fields (field (name "PARTNO") "DNP"))
      (libsource (lib "eagle-import") (part "TEST-POINT'4545'"))
    )
    (comp (ref "POR")
      (value "TEST-POINT'4545'")
      (footprint "eagle-import:TP-D45MIL")
      (fields (field (name "PARTNO") "DNP"))
      (libsource (lib "eagle-import") (part "TEST-POINT'4545'"))
    )
    (comp (ref "Q1")
      (value "CJ2102")
      (footprint "eagle-import:SOT-323")
      (libsource (lib "eagle-import") (part "MOSFET-N+'SI1304BDL'"))
    )
    (comp (ref "R1")
      (value "33R")
      (footprint "eagle-import:R0402")
      (libsource (lib "eagle-import") (part "Discrete-new_RES-0402"))
    )
    (comp (ref "R2")
      (value "10K")
      (footprint "eagle-import:R0402")
      (libsource (lib "eagle-import") (part "Discrete-new_RES-0402"))
    )
    (comp (ref "R3")
      (value "10k")
      (footprint "eagle-import:R0402")
      (libsource (lib "eagle-import") (part "Discrete-new_RES-0402"))
    )
    (comp (ref "R4")
      (value "0R")
      (footprint "eagle-import:R0402")
      (libsource (lib "eagle-import") (part "Discrete-new_RES-0402"))
    )
    (comp (ref "R5")
      (value "100K_1%")
      (footprint "eagle-import:R0402")
      (libsource (lib "eagle-import") (part "Discrete-new_RES-0402"))
    )
    (comp (ref "R6")
      (value "43.2R")
      (footprint "eagle-import:R0402")
      (libsource (lib "eagle-import") (part "Discrete-new_RES-0402"))
    )
    (comp (ref "R7")
      (value "22K_1%")
      (footprint "eagle-import:R0402")
      (libsource (lib "eagle-import") (part "Discrete-new_RES-0402"))
    )
    (comp (ref "R8")
      (value "0R")
      (footprint "eagle-import:R0402")
      (libsource (lib "eagle-import") (part "Discrete-new_RES-0402"))
    )
    (comp (ref "R9")
      (value "0R")
      (footprint "eagle-import:R0402")
      (libsource (lib "eagle-import") (part "Discrete-new_RES-0402"))
    )
    (comp (ref "R10")
      (value "20K_1%")
      (footprint "eagle-import:R0402")
      (libsource (lib "eagle-import") (part "Discrete-new_RES-0402"))
    )
    (comp (ref "R11")
      (value "30K_1%")
      (footprint "eagle-import:R0402")
      (libsource (lib "eagle-import") (part "Discrete-new_RES-0402"))
    )
    (comp (ref "R12")
      (value "33R")
      (footprint "eagle-import:R0402")
      (libsource (lib "eagle-import") (part "Discrete-new_RES-0402"))
    )
    (comp (ref "R13")
      (value "4.7R")
      (footprint "eagle-import:R0805")
      (libsource (lib "eagle-import") (part "Discrete-new_RES-0805"))
    )
    (comp (ref "R14")
      (value "33R")
      (footprint "eagle-import:R0402")
      (libsource (lib "eagle-import") (part "Discrete-new_RES-0402"))
    )
    (comp (ref "R15")
      (value "10k")
      (footprint "eagle-import:R0402")
      (libsource (lib "eagle-import") (part "Discrete-new_RES-0402"))
    )
    (comp (ref "R16")
      (value "10k")
      (footprint "eagle-import:R0402")
      (libsource (lib "eagle-import") (part "Discrete-new_RES-0402"))
    )
    (comp (ref "R17")
      (value "1k")
      (footprint "eagle-import:R0402")
      (libsource (lib "eagle-import") (part "Discrete-new_RES-0402"))
    )
    (comp (ref "R18")
      (value "33R")
      (footprint "eagle-import:R0402")
      (libsource (lib "eagle-import") (part "Discrete-new_RES-0402"))
    )
    (comp (ref "R19")
      (value "33R")
      (footprint "eagle-import:R0402")
      (libsource (lib "eagle-import") (part "Discrete-new_RES-0402"))
    )
    (comp (ref "R20")
      (value "100k")
      (footprint "eagle-import:R0402")
      (libsource (lib "eagle-import") (part "Discrete-new_RES-0402"))
    )
    (comp (ref "R21")
      (value "10K")
      (footprint "eagle-import:R0402")
      (libsource (lib "eagle-import") (part "Discrete-new_RES-0402"))
    )
    (comp (ref "R22")
      (value "10K")
      (footprint "eagle-import:R0402")
      (libsource (lib "eagle-import") (part "Discrete-new_RES-0402"))
    )
    (comp (ref "R23")
      (value "3.9k")
      (footprint "eagle-import:R0402")
      (libsource (lib "eagle-import") (part "Discrete-new_RES-0402"))
    )
    (comp (ref "R24")
      (value "10K")
      (footprint "eagle-import:R0402")
      (libsource (lib "eagle-import") (part "Discrete-new_RES-0402"))
    )
    (comp (ref "R25")
      (value "470R")
      (footprint "eagle-import:R0402")
      (libsource (lib "eagle-import") (part "Discrete-new_RES-0402"))
    )
    (comp (ref "R26")
      (value "33R")
      (footprint "eagle-import:R0402")
      (libsource (lib "eagle-import") (part "RES-0402"))
    )
    (comp (ref "R27")
      (value "10K")
      (footprint "eagle-import:R0402")
      (libsource (lib "eagle-import") (part "Discrete-new_RES-0402"))
    )
    (comp (ref "R28")
      (value "33R")
      (footprint "eagle-import:R0402")
      (libsource (lib "eagle-import") (part "RES-0402"))
    )
    (comp (ref "R29")
      (value "33R")
      (footprint "eagle-import:R0402")
      (libsource (lib "eagle-import") (part "RES-0402"))
    )
    (comp (ref "R30")
      (value "33R")
      (footprint "eagle-import:R0402")
      (libsource (lib "eagle-import") (part "RES-0402"))
    )
    (comp (ref "R31")
      (value "33R")
      (footprint "eagle-import:R0402")
      (libsource (lib "eagle-import") (part "RES-0402"))
    )
    (comp (ref "R32")
      (value "0R")
      (footprint "eagle-import:R0402")
      (libsource (lib "eagle-import") (part "Discrete-new_RES-0402"))
    )
    (comp (ref "R33")
      (value "33R")
      (footprint "eagle-import:R0402")
      (libsource (lib "eagle-import") (part "Discrete-new_RES-0402"))
    )
    (comp (ref "R34")
      (value "470R")
      (footprint "eagle-import:R0402")
      (libsource (lib "eagle-import") (part "Discrete-new_RES-0402"))
    )
    (comp (ref "R35")
      (value "10K")
      (footprint "eagle-import:R0402")
      (libsource (lib "eagle-import") (part "Discrete-new_RES-0402"))
    )
    (comp (ref "R36")
      (value "0R DNP")
      (footprint "eagle-import:R0402")
      (libsource (lib "eagle-import") (part "Discrete-new_RES-0402"))
    )
    (comp (ref "R37")
      (value "0R DNP")
      (footprint "eagle-import:R0402")
      (libsource (lib "eagle-import") (part "Discrete-new_RES-0402"))
    )
    (comp (ref "R38")
      (value "0R")
      (footprint "eagle-import:R0402")
      (libsource (lib "eagle-import") (part "Discrete-new_RES-0402"))
    )
    (comp (ref "R39")
      (value "10k")
      (footprint "eagle-import:R0402")
      (libsource (lib "eagle-import") (part "Discrete-new_RES-0402"))
    )
    (comp (ref "R40")
      (value "33R")
      (footprint "eagle-import:R0402")
      (libsource (lib "eagle-import") (part "Discrete-new_RES-0402"))
    )
    (comp (ref "R41")
      (value "33R")
      (footprint "eagle-import:R0402")
      (libsource (lib "eagle-import") (part "Discrete-new_RES-0402"))
    )
    (comp (ref "R42")
      (value "DNP 0R")
      (footprint "eagle-import:R0402")
      (libsource (lib "eagle-import") (part "RES-0402"))
    )
    (comp (ref "R43")
      (value "DNP 10K")
      (footprint "eagle-import:R0402")
      (libsource (lib "eagle-import") (part "Discrete-new_RES-0402"))
    )
    (comp (ref "R44")
      (value "33R")
      (footprint "eagle-import:R0402")
      (libsource (lib "eagle-import") (part "Discrete-new_RES-0402"))
    )
    (comp (ref "R45")
      (value "10K")
      (footprint "eagle-import:R0402")
      (libsource (lib "eagle-import") (part "Discrete-new_RES-0402"))
    )
    (comp (ref "R46")
      (value "33R")
      (footprint "eagle-import:R0402")
      (libsource (lib "eagle-import") (part "Discrete-new_RES-0402"))
    )
    (comp (ref "R47")
      (value "33R")
      (footprint "eagle-import:R0402")
      (libsource (lib "eagle-import") (part "Discrete-new_RES-0402"))
    )
    (comp (ref "R48")
      (value "33R")
      (footprint "eagle-import:R0402")
      (libsource (lib "eagle-import") (part "Discrete-new_RES-0402"))
    )
    (comp (ref "R49")
      (value "33R")
      (footprint "eagle-import:R0402")
      (libsource (lib "eagle-import") (part "Discrete-new_RES-0402"))
    )
    (comp (ref "R50")
      (value "33R")
      (footprint "eagle-import:R0402")
      (libsource (lib "eagle-import") (part "Discrete-new_RES-0402"))
    )
    (comp (ref "R52")
      (value "33R")
      (footprint "eagle-import:R0402")
      (libsource (lib "eagle-import") (part "RES-0402"))
    )
    (comp (ref "R53")
      (value "33R")
      (footprint "eagle-import:R0402")
      (libsource (lib "eagle-import") (part "RES-0402"))
    )
    (comp (ref "R58")
      (value "33R")
      (footprint "eagle-import:R0402")
      (libsource (lib "eagle-import") (part "Discrete-new_RES-0402"))
    )
    (comp (ref "R60")
      (value "33R")
      (footprint "eagle-import:R0402")
      (libsource (lib "eagle-import") (part "Discrete-new_RES-0402"))
    )
    (comp (ref "R61")
      (value "33R")
      (footprint "eagle-import:R0402")
      (libsource (lib "eagle-import") (part "Discrete-new_RES-0402"))
    )
    (comp (ref "R62")
      (value "33R")
      (footprint "eagle-import:R0402")
      (libsource (lib "eagle-import") (part "Discrete-new_RES-0402"))
    )
    (comp (ref "R63")
      (value "33R")
      (footprint "eagle-import:R0402")
      (libsource (lib "eagle-import") (part "Discrete-new_RES-0402"))
    )
    (comp (ref "R64")
      (value "33R")
      (footprint "eagle-import:R0402")
      (libsource (lib "eagle-import") (part "Discrete-new_RES-0402"))
    )
    (comp (ref "R65")
      (value "33R")
      (footprint "eagle-import:R0402")
      (libsource (lib "eagle-import") (part "Discrete-new_RES-0402"))
    )
    (comp (ref "RST")
      (value "TEST-POINT'4545'")
      (footprint "eagle-import:TP-D45MIL")
      (fields (field (name "PARTNO") "DNP"))
      (libsource (lib "eagle-import") (part "TEST-POINT'4545'"))
    )
    (comp (ref "RST_N")
      (value "TEST-POINT'4545'")
      (footprint "eagle-import:TP-D45MIL")
      (fields (field (name "PARTNO") "DNP"))
      (libsource (lib "eagle-import") (part "TEST-POINT'4545'"))
    )
    (comp (ref "SK0")
      (value "SK6812MINI")
      (footprint "eagle-import:LED4-SMD-3.5X3.7MM")
      (libsource (lib "eagle-import") (part "LED-RGB-4P-SK68122"))
    )
    (comp (ref "SK1")
      (value "SK6812MINI")
      (footprint "eagle-import:LED4-SMD-3.5X3.7MM")
      (libsource (lib "eagle-import") (part "LED-RGB-4P-SK68122"))
    )
    (comp (ref "SK2")
      (value "SK6812MINI")
      (footprint "eagle-import:LED4-SMD-3.5X3.7MM")
      (libsource (lib "eagle-import") (part "LED-RGB-4P-SK68122"))
    )
    (comp (ref "SK3")
      (value "SK6812MINI")
      (footprint "eagle-import:LED4-SMD-3.5X3.7MM")
      (libsource (lib "eagle-import") (part "LED-RGB-4P-SK68122"))
    )
    (comp (ref "SK4")
      (value "SK6812MINI")
      (footprint "eagle-import:LED4-SMD-3.5X3.7MM")
      (libsource (lib "eagle-import") (part "LED-RGB-4P-SK68122"))
    )
    (comp (ref "SK5")
      (value "SK6812MINI")
      (footprint "eagle-import:LED4-SMD-3.5X3.7MM")
      (libsource (lib "eagle-import") (part "LED-RGB-4P-SK68122"))
    )
    (comp (ref "SK6")
      (value "SK6812MINI")
      (footprint "eagle-import:LED4-SMD-3.5X3.7MM")
      (libsource (lib "eagle-import") (part "LED-RGB-4P-SK68122"))
    )
    (comp (ref "SK7")
      (value "SK6812MINI")
      (footprint "eagle-import:LED4-SMD-3.5X3.7MM")
      (libsource (lib "eagle-import") (part "LED-RGB-4P-SK68122"))
    )
    (comp (ref "SK8")
      (value "SK6812MINI")
      (footprint "eagle-import:LED4-SMD-3.5X3.7MM")
      (libsource (lib "eagle-import") (part "LED-RGB-4P-SK68122"))
    )
    (comp (ref "SK9")
      (value "SK6812MINI")
      (footprint "eagle-import:LED4-SMD-3.5X3.7MM")
      (libsource (lib "eagle-import") (part "LED-RGB-4P-SK68122"))
    )
    (comp (ref "SK10")
      (value "SK6812MINI")
      (footprint "eagle-import:LED4-SMD-3.5X3.7MM")
      (libsource (lib "eagle-import") (part "LED-RGB-4P-SK68122"))
    )
    (comp (ref "SK11")
      (value "SK6812MINI")
      (footprint "eagle-import:LED4-SMD-3.5X3.7MM")
      (libsource (lib "eagle-import") (part "LED-RGB-4P-SK68122"))
    )
    (comp (ref "SW1")
      (value "FSA2275")
      (footprint "eagle-import:LEAD12P-SMD-0.4-1.8X1.8X0.5MM")
      (libsource (lib "eagle-import") (part "SWITCH-ANALOG-FSA2275"))
    )
    (comp (ref "TCK")
      (value "TEST-POINT'4545'")
      (footprint "eagle-import:TP-D45MIL")
      (fields (field (name "PARTNO") "DNP"))
      (libsource (lib "eagle-import") (part "TEST-POINT'4545'"))
    )
    (comp (ref "TDI")
      (value "TEST-POINT'4545'")
      (footprint "eagle-import:TP-D45MIL")
      (fields (field (name "PARTNO") "DNP"))
      (libsource (lib "eagle-import") (part "TEST-POINT'4545'"))
    )
    (comp (ref "TDO")
      (value "TEST-POINT'4545'")
      (footprint "eagle-import:TP-D45MIL")
      (fields (field (name "PARTNO") "DNP"))
      (libsource (lib "eagle-import") (part "TEST-POINT'4545'"))
    )
    (comp (ref "TMS")
      (value "TEST-POINT'4545'")
      (footprint "eagle-import:TP-D45MIL")
      (fields (field (name "PARTNO") "DNP"))
      (libsource (lib "eagle-import") (part "TEST-POINT'4545'"))
    )
    (comp (ref "TP4")
      (value "TEST-POINT'4545'")
      (footprint "eagle-import:TP-D45MIL")
      (fields (field (name "PARTNO") "DNP"))
      (libsource (lib "eagle-import") (part "TEST-POINT'4545'"))
    )
    (comp (ref "TP14")
      (value "TEST-POINT'4545'")
      (footprint "eagle-import:TP-D45MIL")
      (fields (field (name "PARTNO") "DNP"))
      (libsource (lib "eagle-import") (part "TEST-POINT'4545'"))
    )
    (comp (ref "U1")
      (value "XVSM-2000")
      (footprint "eagle-import:TQFP128-0.4-14X14MM")
      (libsource (lib "eagle-import") (part "MCU-XUF216-512-TQ128"))
    )
    (comp (ref "U2")
      (value "ETA3410")
      (footprint "eagle-import:DFN8G-0.5-2X2MM")
      (libsource (lib "eagle-import") (part "CONVERTER-ETA3410"))
    )
    (comp (ref "U3")
      (value "ETA3410")
      (footprint "eagle-import:DFN8G-0.5-2X2MM")
      (libsource (lib "eagle-import") (part "CONVERTER-ETA3410"))
    )
    (comp (ref "U4")
      (value "74HC1G08")
      (footprint "eagle-import:SOT-353")
      (libsource (lib "eagle-import") (part "LOGIC-74HC1G08'GW'"))
    )
    (comp (ref "U5")
      (value "ADM1085")
      (footprint "eagle-import:SC-70-6")
      (libsource (lib "eagle-import") (part "ANALOG-DEVICE-ADM1085"))
    )
    (comp (ref "U6")
      (value "WM8960")
      (footprint "eagle-import:QFN32G-0.5-5X5MM")
      (libsource (lib "eagle-import") (part "AMPLIFIER-WM8960"))
    )
    (comp (ref "U7")
      (value "AP7333")
      (footprint "eagle-import:SOT-23")
      (libsource (lib "eagle-import") (part "PMIC-XC6206PMR"))
    )
    (comp (ref "U8")
      (value "74AHC1G79")
      (footprint "eagle-import:SOT-353")
      (libsource (lib "eagle-import") (part "LOGIC-74AHC/T1G79"))
    )
    (comp (ref "U9")
      (value "NC7NZ34")
      (footprint "eagle-import:US-8")
      (libsource (lib "eagle-import") (part "LOGIC-NC7NZ34"))
    )
    (comp (ref "U10")
      (value "NC7NZ34")
      (footprint "eagle-import:US-8")
      (libsource (lib "eagle-import") (part "LOGIC-NC7NZ34"))
    )
    (comp (ref "U11")
      (value "NC7NZ34")
      (footprint "eagle-import:US-8")
      (libsource (lib "eagle-import") (part "LOGIC-NC7NZ34"))
    )
    (comp (ref "U12")
      (value "NC7NZ34")
      (footprint "eagle-import:US-8")
      (libsource (lib "eagle-import") (part "LOGIC-NC7NZ34"))
    )
    (comp (ref "U13")
      (value "74HC1G08")
      (footprint "eagle-import:SOT-353")
      (libsource (lib "eagle-import") (part "LOGIC-74HC1G08'GW'"))
    )
    (comp (ref "X1")
      (value "24MHz")
      (footprint "eagle-import:OSC-SMD-2.5X2.0X0.9MM")
      (libsource (lib "eagle-import") (part "CRYSTAL-OSCILLATOR-NZ2520"))
    )
    (comp (ref "X2")
      (value "24MHz")
      (footprint "eagle-import:OSC-SMD-2.5X2.0X0.9MM")
      (libsource (lib "eagle-import") (part "CRYSTAL-OSCILLATOR-NZ2520"))
    )
    (comp (ref "XL_DN0")
      (value "TEST-POINT'4545'")
      (footprint "eagle-import:TP-D45MIL")
      (fields (field (name "PARTNO") "DNP"))
      (libsource (lib "eagle-import") (part "TEST-POINT'4545'"))
    )
    (comp (ref "XL_DN1")
      (value "TEST-POINT'4545'")
      (footprint "eagle-import:TP-D45MIL")
      (fields (field (name "PARTNO") "DNP"))
      (libsource (lib "eagle-import") (part "TEST-POINT'4545'"))
    )
    (comp (ref "XL_UP0")
      (value "TEST-POINT'4545'")
      (footprint "eagle-import:TP-D45MIL")
      (fields (field (name "PARTNO") "DNP"))
      (libsource (lib "eagle-import") (part "TEST-POINT'4545'"))
    )
    (comp (ref "XL_UP1")
      (value "TEST-POINT'4545'")
      (footprint "eagle-import:TP-D45MIL")
      (fields (field (name "PARTNO") "DNP"))
      (libsource (lib "eagle-import") (part "TEST-POINT'4545'"))
    )
  )
  (nets
    (net (code "1") (name "24MHZ") (class "Default")
      (node (ref "24M") (pin "T") (pinfunction "T_T") (pintype "bidirectional"))
      (node (ref "R1") (pin "2") (pinfunction "2_2") (pintype "passive"))
      (node (ref "U1") (pin "125") (pinfunction "CLK_125") (pintype "bidirectional"))
    )
    (net (code "2") (name "24MHZ_8960") (class "Default")
      (node (ref "24M_1") (pin "T") (pinfunction "T_T") (pintype "bidirectional"))
      (node (ref "R19") (pin "2") (pinfunction "2_2") (pintype "passive"))
      (node (ref "U6") (pin "11") (pinfunction "MCLK_11") (pintype "bidirectional"))
    )
    (net (code "3") (name "AUX_SEL") (class "Default")
      (node (ref "J3") (pin "1") (pinfunction "1_1") (pintype "bidirectional"))
      (node (ref "J6") (pin "2") (pinfunction "2_2") (pintype "bidirectional"))
      (node (ref "R20") (pin "2") (pinfunction "2_2") (pintype "passive"))
      (node (ref "SW1") (pin "6") (pinfunction "SEL_6") (pintype "bidirectional"))
    )
    (net (code "4") (name "AVDD") (class "Default")
      (node (ref "C68") (pin "2") (pinfunction "2_2") (pintype "passive"))
      (node (ref "C71") (pin "2") (pinfunction "2_2") (pintype "passive"))
      (node (ref "C79") (pin "2") (pinfunction "2_2") (pintype "passive"))
      (node (ref "C89") (pin "2") (pinfunction "2_2") (pintype "passive"))
      (node (ref "R20") (pin "1") (pinfunction "1_1") (pintype "passive"))
      (node (ref "SW1") (pin "1") (pinfunction "VDD_1") (pintype "bidirectional"))
      (node (ref "TP4") (pin "T") (pinfunction "T_T") (pintype "bidirectional"))
      (node (ref "U6") (pin "32") (pinfunction "AVDD_32") (pintype "bidirectional"))
      (node (ref "U7") (pin "2") (pinfunction "VOUT_2") (pintype "bidirectional"))
    )
    (net (code "5") (name "CENTRAL_LED") (class "Default")
      (node (ref "J3") (pin "4") (pinfunction "4_4") (pintype "bidirectional"))
      (node (ref "J6") (pin "3") (pinfunction "3_3") (pintype "bidirectional"))
      (node (ref "R34") (pin "2") (pinfunction "2_2") (pintype "passive"))
      (node (ref "U1") (pin "32") (pinfunction "X0D11_32") (pintype "bidirectional"))
    )
    (net (code "6") (name "DEBUG_USBDM_N") (class "Default")
      (node (ref "D7") (pin "1") (pinfunction "2_1") (pintype "bidirectional"))
      (node (ref "DM") (pin "T") (pinfunction "T_T") (pintype "bidirectional"))
      (node (ref "J1") (pin "2") (pinfunction "DM_2") (pintype "bidirectional"))
      (node (ref "R38") (pin "2") (pinfunction "2_2") (pintype "passive"))
    )
    (net (code "7") (name "DEBUG_USBDP_P") (class "Default")
      (node (ref "D8") (pin "1") (pinfunction "2_1") (pintype "bidirectional"))
      (node (ref "DP") (pin "T") (pinfunction "T_T") (pintype "bidirectional"))
      (node (ref "J1") (pin "3") (pinfunction "DP_3") (pintype "bidirectional"))
      (node (ref "R4") (pin "2") (pinfunction "2_2") (pintype "passive"))
    )
    (net (code "8") (name "DOUT5") (class "Default")
      (node (ref "SK6") (pin "1") (pinfunction "DOUT_1") (pintype "bidirectional"))
      (node (ref "SK7") (pin "3") (pinfunction "DIN_3") (pintype "bidirectional"))
    )
    (net (code "9") (name "GND") (class "Default")
      (node (ref "C1") (pin "1") (pinfunction "1_1") (pintype "passive"))
      (node (ref "C10") (pin "1") (pinfunction "1_1") (pintype "passive"))
      (node (ref "C100") (pin "2") (pinfunction "2_2") (pintype "passive"))
      (node (ref "C101") (pin "1") (pinfunction "1_1") (pintype "passive"))
      (node (ref "C103") (pin "1") (pinfunction "1_1") (pintype "passive"))
      (node (ref "C104") (pin "1") (pinfunction "1_1") (pintype "passive"))
      (node (ref "C105") (pin "1") (pinfunction "1_1") (pintype "passive"))
      (node (ref "C106") (pin "1") (pinfunction "1_1") (pintype "passive"))
      (node (ref "C107") (pin "1") (pinfunction "1_1") (pintype "passive"))
      (node (ref "C108") (pin "1") (pinfunction "1_1") (pintype "passive"))
      (node (ref "C109") (pin "1") (pinfunction "1_1") (pintype "passive"))
      (node (ref "C11") (pin "1") (pinfunction "1_1") (pintype "passive"))
      (node (ref "C110") (pin "1") (pinfunction "1_1") (pintype "passive"))
      (node (ref "C111") (pin "1") (pinfunction "1_1") (pintype "passive"))
      (node (ref "C112") (pin "1") (pinfunction "1_1") (pintype "passive"))
      (node (ref "C113") (pin "1") (pinfunction "1_1") (pintype "passive"))
      (node (ref "C114") (pin "1") (pinfunction "1_1") (pintype "passive"))
      (node (ref "C115") (pin "1") (pinfunction "1_1") (pintype "passive"))
      (node (ref "C12") (pin "1") (pinfunction "1_1") (pintype "passive"))
      (node (ref "C13") (pin "1") (pinfunction "1_1") (pintype "passive"))
      (node (ref "C14") (pin "1") (pinfunction "1_1") (pintype "passive"))
      (node (ref "C15") (pin "1") (pinfunction "1_1") (pintype "passive"))
      (node (ref "C16") (pin "1") (pinfunction "1_1") (pintype "passive"))
      (node (ref "C17") (pin "1") (pinfunction "1_1") (pintype "passive"))
      (node (ref "C18") (pin "1") (pinfunction "1_1") (pintype "passive"))
      (node (ref "C19") (pin "1") (pinfunction "1_1") (pintype "passive"))
      (node (ref "C2") (pin "1") (pinfunction "1_1") (pintype "passive"))
      (node (ref "C20") (pin "1") (pinfunction "1_1") (pintype "passive"))
      (node (ref "C21") (pin "1") (pinfunction "1_1") (pintype "passive"))
      (node (ref "C22") (pin "1") (pinfunction "1_1") (pintype "passive"))
      (node (ref "C23") (pin "1") (pinfunction "1_1") (pintype "passive"))
      (node (ref "C24") (pin "1") (pinfunction "1_1") (pintype "passive"))
      (node (ref "C25") (pin "1") (pinfunction "1_1") (pintype "passive"))
      (node (ref "C26") (pin "1") (pinfunction "1_1") (pintype "passive"))
      (node (ref "C27") (pin "1") (pinfunction "1_1") (pintype "passive"))
      (node (ref "C28") (pin "1") (pinfunction "1_1") (pintype "passive"))
      (node (ref "C29") (pin "1") (pinfunction "1_1") (pintype "passive"))
      (node (ref "C3") (pin "1") (pinfunction "1_1") (pintype "passive"))
      (node (ref "C30") (pin "1") (pinfunction "1_1") (pintype "passive"))
      (node (ref "C31") (pin "1") (pinfunction "1_1") (pintype "passive"))
      (node (ref "C32") (pin "1") (pinfunction "1_1") (pintype "passive"))
      (node (ref "C33") (pin "1") (pinfunction "1_1") (pintype "passive"))
      (node (ref "C34") (pin "1") (pinfunction "1_1") (pintype "passive"))
      (node (ref "C35") (pin "1") (pinfunction "1_1") (pintype "passive"))
      (node (ref "C36") (pin "1") (pinfunction "1_1") (pintype "passive"))
      (node (ref "C37") (pin "1") (pinfunction "1_1") (pintype "passive"))
      (node (ref "C38") (pin "1") (pinfunction "1_1") (pintype "passive"))
      (node (ref "C39") (pin "1") (pinfunction "1_1") (pintype "passive"))
      (node (ref "C40") (pin "1") (pinfunction "1_1") (pintype "passive"))
      (node (ref "C41") (pin "1") (pinfunction "1_1") (pintype "passive"))
      (node (ref "C42") (pin "1") (pinfunction "1_1") (pintype "passive"))
      (node (ref "C43") (pin "1") (pinfunction "1_1") (pintype "passive"))
      (node (ref "C44") (pin "1") (pinfunction "1_1") (pintype "passive"))
      (node (ref "C45") (pin "1") (pinfunction "1_1") (pintype "passive"))
      (node (ref "C46") (pin "1") (pinfunction "1_1") (pintype "passive"))
      (node (ref "C47") (pin "1") (pinfunction "1_1") (pintype "passive"))
      (node (ref "C48") (pin "1") (pinfunction "1_1") (pintype "passive"))
      (node (ref "C49") (pin "1") (pinfunction "1_1") (pintype "passive"))
      (node (ref "C5") (pin "1") (pinfunction "1_1") (pintype "passive"))
      (node (ref "C50") (pin "1") (pinfunction "1_1") (pintype "passive"))
      (node (ref "C51") (pin "1") (pinfunction "1_1") (pintype "passive"))
      (node (ref "C52") (pin "1") (pinfunction "1_1") (pintype "passive"))
      (node (ref "C53") (pin "1") (pinfunction "1_1") (pintype "passive"))
      (node (ref "C54") (pin "1") (pinfunction "1_1") (pintype "passive"))
      (node (ref "C55") (pin "1") (pinfunction "1_1") (pintype "passive"))
      (node (ref "C56") (pin "1") (pinfunction "1_1") (pintype "passive"))
      (node (ref "C57") (pin "1") (pinfunction "1_1") (pintype "passive"))
      (node (ref "C58") (pin "1") (pinfunction "1_1") (pintype "passive"))
      (node (ref "C59") (pin "1") (pinfunction "1_1") (pintype "passive"))
      (node (ref "C6") (pin "1") (pinfunction "1_1") (pintype "passive"))
      (node (ref "C60") (pin "1") (pinfunction "1_1") (pintype "passive"))
      (node (ref "C61") (pin "1") (pinfunction "1_1") (pintype "passive"))
      (node (ref "C62") (pin "1") (pinfunction "1_1") (pintype "passive"))
      (node (ref "C63") (pin "1") (pinfunction "1_1") (pintype "passive"))
      (node (ref "C64") (pin "1") (pinfunction "1_1") (pintype "passive"))
      (node (ref "C65") (pin "1") (pinfunction "1_1") (pintype "passive"))
      (node (ref "C66") (pin "1") (pinfunction "1_1") (pintype "passive"))
      (node (ref "C67") (pin "1") (pinfunction "1_1") (pintype "passive"))
      (node (ref "C69") (pin "1") (pinfunction "1_1") (pintype "passive"))
      (node (ref "C7") (pin "1") (pinfunction "1_1") (pintype "passive"))
      (node (ref "C70") (pin "1") (pinfunction "1_1") (pintype "passive"))
      (node (ref "C72") (pin "1") (pinfunction "1_1") (pintype "passive"))
      (node (ref "C73") (pin "1") (pinfunction "1_1") (pintype "passive"))
      (node (ref "C74") (pin "1") (pinfunction "1_1") (pintype "passive"))
      (node (ref "C75") (pin "1") (pinfunction "1_1") (pintype "passive"))
      (node (ref "C76") (pin "1") (pinfunction "1_1") (pintype "passive"))
      (node (ref "C77") (pin "2") (pinfunction "2_2") (pintype "passive"))
      (node (ref "C78") (pin "1") (pinfunction "1_1") (pintype "passive"))
      (node (ref "C8") (pin "1") (pinfunction "1_1") (pintype "passive"))
      (node (ref "C80") (pin "2") (pinfunction "2_2") (pintype "passive"))
      (node (ref "C82") (pin "2") (pinfunction "2_2") (pintype "passive"))
      (node (ref "C83") (pin "2") (pinfunction "2_2") (pintype "passive"))
      (node (ref "C84") (pin "1") (pinfunction "1_1") (pintype "passive"))
      (node (ref "C85") (pin "1") (pinfunction "1_1") (pintype "passive"))
      (node (ref "C86") (pin "1") (pinfunction "1_1") (pintype "passive"))
      (node (ref "C87") (pin "1") (pinfunction "1_1") (pintype "passive"))
      (node (ref "C88") (pin "1") (pinfunction "1_1") (pintype "passive"))
      (node (ref "C9") (pin "1") (pinfunction "1_1") (pintype "passive"))
      (node (ref "C94") (pin "1") (pinfunction "1_1") (pintype "passive"))
      (node (ref "C95") (pin "1") (pinfunction "1_1") (pintype "passive"))
      (node (ref "C96") (pin "1") (pinfunction "1_1") (pintype "passive"))
      (node (ref "C98") (pin "1") (pinfunction "1_1") (pintype "passive"))
      (node (ref "C99") (pin "1") (pinfunction "1_1") (pintype "passive"))
      (node (ref "D7") (pin "2") (pinfunction "1_2") (pintype "bidirectional"))
      (node (ref "D8") (pin "2") (pinfunction "1_2") (pintype "bidirectional"))
      (node (ref "D9") (pin "-") (pinfunction "-_-") (pintype "passive"))
      (node (ref "GND") (pin "T") (pinfunction "T_T") (pintype "bidirectional"))
      (node (ref "J1") (pin "5") (pinfunction "GND_5") (pintype "bidirectional"))
      (node (ref "J1") (pin "S1") (pinfunction "GND_S1") (pintype "bidirectional"))
      (node (ref "J1") (pin "S2") (pinfunction "GND_S2") (pintype "bidirectional"))
      (node (ref "J1") (pin "S3") (pinfunction "GND_S3") (pintype "bidirectional"))
      (node (ref "J1") (pin "S4") (pinfunction "GND_S4") (pintype "bidirectional"))
      (node (ref "J1") (pin "S5") (pinfunction "GND_S5") (pintype "bidirectional"))
      (node (ref "J1") (pin "S6") (pinfunction "GND_S6") (pintype "bidirectional"))
      (node (ref "J3") (pin "15") (pinfunction "15_15") (pintype "bidirectional"))
      (node (ref "J4") (pin "1") (pinfunction "1_1") (pintype "bidirectional"))
      (node (ref "J6") (pin "16") (pinfunction "16_16") (pintype "bidirectional"))
      (node (ref "L5") (pin "1") (pinfunction "1_1") (pintype "passive"))
      (node (ref "MIC10") (pin "2") (pinfunction "LR_2") (pintype "bidirectional"))
      (node (ref "MIC10") (pin "5") (pinfunction "GND_5") (pintype "bidirectional"))
      (node (ref "MIC10") (pin "6") (pinfunction "GND_6") (pintype "bidirectional"))
      (node (ref "MIC10") (pin "7") (pinfunction "GND_7") (pintype "bidirectional"))
      (node (ref "MIC10") (pin "8") (pinfunction "GND_8") (pintype "bidirectional"))
      (node (ref "MIC11") (pin "2") (pinfunction "LR_2") (pintype "bidirectional"))
      (node (ref "MIC11") (pin "5") (pinfunction "GND_5") (pintype "bidirectional"))
      (node (ref "MIC11") (pin "6") (pinfunction "GND_6") (pintype "bidirectional"))
      (node (ref "MIC11") (pin "7") (pinfunction "GND_7") (pintype "bidirectional"))
      (node (ref "MIC11") (pin "8") (pinfunction "GND_8") (pintype "bidirectional"))
      (node (ref "MIC12") (pin "2") (pinfunction "LR_2") (pintype "bidirectional"))
      (node (ref "MIC12") (pin "5") (pinfunction "GND_5") (pintype "bidirectional"))
      (node (ref "MIC12") (pin "6") (pinfunction "GND_6") (pintype "bidirectional"))
      (node (ref "MIC12") (pin "7") (pinfunction "GND_7") (pintype "bidirectional"))
      (node (ref "MIC12") (pin "8") (pinfunction "GND_8") (pintype "bidirectional"))
      (node (ref "MIC13") (pin "2") (pinfunction "LR_2") (pintype "bidirectional"))
      (node (ref "MIC13") (pin "5") (pinfunction "GND_5") (pintype "bidirectional"))
      (node (ref "MIC13") (pin "6") (pinfunction "GND_6") (pintype "bidirectional"))
      (node (ref "MIC13") (pin "7") (pinfunction "GND_7") (pintype "bidirectional"))
      (node (ref "MIC13") (pin "8") (pinfunction "GND_8") (pintype "bidirectional"))
      (node (ref "MIC7") (pin "2") (pinfunction "LR_2") (pintype "bidirectional"))
      (node (ref "MIC7") (pin "5") (pinfunction "GND_5") (pintype "bidirectional"))
      (node (ref "MIC7") (pin "6") (pinfunction "GND_6") (pintype "bidirectional"))
      (node (ref "MIC7") (pin "7") (pinfunction "GND_7") (pintype "bidirectional"))
      (node (ref "MIC7") (pin "8") (pinfunction "GND_8") (pintype "bidirectional"))
      (node (ref "MIC8") (pin "2") (pinfunction "LR_2") (pintype "bidirectional"))
      (node (ref "MIC8") (pin "5") (pinfunction "GND_5") (pintype "bidirectional"))
      (node (ref "MIC8") (pin "6") (pinfunction "GND_6") (pintype "bidirectional"))
      (node (ref "MIC8") (pin "7") (pinfunction "GND_7") (pintype "bidirectional"))
      (node (ref "MIC8") (pin "8") (pinfunction "GND_8") (pintype "bidirectional"))
      (node (ref "MIC9") (pin "2") (pinfunction "LR_2") (pintype "bidirectional"))
      (node (ref "MIC9") (pin "5") (pinfunction "GND_5") (pintype "bidirectional"))
      (node (ref "MIC9") (pin "6") (pinfunction "GND_6") (pintype "bidirectional"))
      (node (ref "MIC9") (pin "7") (pinfunction "GND_7") (pintype "bidirectional"))
      (node (ref "MIC9") (pin "8") (pinfunction "GND_8") (pintype "bidirectional"))
      (node (ref "Q1") (pin "2") (pinfunction "S_2") (pintype "passive"))
      (node (ref "R11") (pin "1") (pinfunction "1_1") (pintype "passive"))
      (node (ref "R22") (pin "1") (pinfunction "1_1") (pintype "passive"))
      (node (ref "R32") (pin "1") (pinfunction "1_1") (pintype "passive"))
      (node (ref "R45") (pin "1") (pinfunction "1_1") (pintype "passive"))
      (node (ref "R6") (pin "1") (pinfunction "1_1") (pintype "passive"))
      (node (ref "R7") (pin "1") (pinfunction "1_1") (pintype "passive"))
      (node (ref "SK0") (pin "2") (pinfunction "VSS_2") (pintype "bidirectional"))
      (node (ref "SK1") (pin "2") (pinfunction "VSS_2") (pintype "bidirectional"))
      (node (ref "SK10") (pin "2") (pinfunction "VSS_2") (pintype "bidirectional"))
      (node (ref "SK11") (pin "2") (pinfunction "VSS_2") (pintype "bidirectional"))
      (node (ref "SK2") (pin "2") (pinfunction "VSS_2") (pintype "bidirectional"))
      (node (ref "SK3") (pin "2") (pinfunction "VSS_2") (pintype "bidirectional"))
      (node (ref "SK4") (pin "2") (pinfunction "VSS_2") (pintype "bidirectional"))
      (node (ref "SK5") (pin "2") (pinfunction "VSS_2") (pintype "bidirectional"))
      (node (ref "SK6") (pin "2") (pinfunction "VSS_2") (pintype "bidirectional"))
      (node (ref "SK7") (pin "2") (pinfunction "VSS_2") (pintype "bidirectional"))
      (node (ref "SK8") (pin "2") (pinfunction "VSS_2") (pintype "bidirectional"))
      (node (ref "SK9") (pin "2") (pinfunction "VSS_2") (pintype "bidirectional"))
      (node (ref "U1") (pin "104") (pinfunction "PLL_AGND_104") (pintype "bidirectional"))
      (node (ref "U1") (pin "PAD") (pinfunction "VSS_PAD") (pintype "bidirectional"))
      (node (ref "U10") (pin "4") (pinfunction "GND_4") (pintype "bidirectional"))
      (node (ref "U11") (pin "4") (pinfunction "GND_4") (pintype "bidirectional"))
      (node (ref "U12") (pin "4") (pinfunction "GND_4") (pintype "bidirectional"))
      (node (ref "U13") (pin "3") (pinfunction "GND_3") (pintype "bidirectional"))
      (node (ref "U2") (pin "1") (pinfunction "PGND_1") (pintype "bidirectional"))
      (node (ref "U2") (pin "3") (pinfunction "AGND_3") (pintype "bidirectional"))
      (node (ref "U2") (pin "6") (pinfunction "MODE_6") (pintype "bidirectional"))
      (node (ref "U2") (pin "9") (pinfunction "PAD_9") (pintype "bidirectional"))
      (node (ref "U3") (pin "1") (pinfunction "PGND_1") (pintype "bidirectional"))
      (node (ref "U3") (pin "3") (pinfunction "AGND_3") (pintype "bidirectional"))
      (node (ref "U3") (pin "6") (pinfunction "MODE_6") (pintype "bidirectional"))
      (node (ref "U3") (pin "9") (pinfunction "PAD_9") (pintype "bidirectional"))
      (node (ref "U4") (pin "3") (pinfunction "GND_3") (pintype "bidirectional"))
      (node (ref "U5") (pin "2") (pinfunction "GND_2") (pintype "bidirectional"))
      (node (ref "U6") (pin "20") (pinfunction "SPKGND2_20") (pintype "bidirectional"))
      (node (ref "U6") (pin "24") (pinfunction "SPKGND1_24") (pintype "bidirectional"))
      (node (ref "U6") (pin "9") (pinfunction "DGND_9") (pintype "bidirectional"))
      (node (ref "U8") (pin "3") (pinfunction "GND_3") (pintype "bidirectional"))
      (node (ref "U9") (pin "4") (pinfunction "GND_4") (pintype "bidirectional"))
      (node (ref "X1") (pin "2") (pinfunction "GND_2") (pintype "bidirectional"))
      (node (ref "X2") (pin "2") (pinfunction "GND_2") (pintype "bidirectional"))
    )
    (net (code "10") (name "GND_SIGNAL") (class "Default")
      (node (ref "C102") (pin "2") (pinfunction "2_2") (pintype "passive"))
      (node (ref "C4") (pin "1") (pinfunction "1_1") (pintype "passive"))
      (node (ref "C68") (pin "1") (pinfunction "1_1") (pintype "passive"))
      (node (ref "C71") (pin "1") (pinfunction "1_1") (pintype "passive"))
      (node (ref "C79") (pin "1") (pinfunction "1_1") (pintype "passive"))
      (node (ref "C81") (pin "1") (pinfunction "1_1") (pintype "passive"))
      (node (ref "C89") (pin "1") (pinfunction "1_1") (pintype "passive"))
      (node (ref "C92") (pin "1") (pinfunction "1_1") (pintype "passive"))
      (node (ref "C93") (pin "1") (pinfunction "1_1") (pintype "passive"))
      (node (ref "D1") (pin "2") (pinfunction "1_2") (pintype "bidirectional"))
      (node (ref "D2") (pin "2") (pinfunction "1_2") (pintype "bidirectional"))
      (node (ref "J3") (pin "14") (pinfunction "14_14") (pintype "bidirectional"))
      (node (ref "J6") (pin "13") (pinfunction "13_13") (pintype "bidirectional"))
      (node (ref "J9") (pin "1") (pinfunction "1_1") (pintype "bidirectional"))
      (node (ref "J9") (pin "2") (pinfunction "2_2") (pintype "bidirectional"))
      (node (ref "J9") (pin "5") (pinfunction "5_5") (pintype "bidirectional"))
      (node (ref "J9") (pin "6") (pinfunction "6_6") (pintype "bidirectional"))
      (node (ref "L5") (pin "2") (pinfunction "2_2") (pintype "passive"))
      (node (ref "R3") (pin "1") (pinfunction "1_1") (pintype "passive"))
      (node (ref "R32") (pin "2") (pinfunction "2_2") (pintype "passive"))
      (node (ref "R39") (pin "1") (pinfunction "1_1") (pintype "passive"))
      (node (ref "SW1") (pin "3") (pinfunction "GND_3") (pintype "bidirectional"))
      (node (ref "SW1") (pin "7") (pinfunction "MUTE_7") (pintype "bidirectional"))
      (node (ref "SW1") (pin "8") (pinfunction "GND_8") (pintype "bidirectional"))
      (node (ref "U6") (pin "28") (pinfunction "AGND_28") (pintype "bidirectional"))
      (node (ref "U6") (pin "33") (pinfunction "GND_33") (pintype "bidirectional"))
      (node (ref "U7") (pin "1") (pinfunction "VSS_1") (pintype "bidirectional"))
    )
    (net (code "11") (name "HP_L") (class "Default")
      (node (ref "D1") (pin "1") (pinfunction "2_1") (pintype "bidirectional"))
      (node (ref "J3") (pin "8") (pinfunction "8_8") (pintype "bidirectional"))
      (node (ref "J6") (pin "7") (pinfunction "7_7") (pintype "bidirectional"))
      (node (ref "L4") (pin "1") (pinfunction "1_1") (pintype "passive"))
      (node (ref "SW1") (pin "4") (pinfunction "LSPKR_4") (pintype "bidirectional"))
    )
    (net (code "12") (name "HP_R") (class "Default")
      (node (ref "D2") (pin "1") (pinfunction "2_1") (pintype "bidirectional"))
      (node (ref "J3") (pin "7") (pinfunction "7_7") (pintype "bidirectional"))
      (node (ref "J6") (pin "8") (pinfunction "8_8") (pintype "bidirectional"))
      (node (ref "L3") (pin "1") (pinfunction "1_1") (pintype "passive"))
      (node (ref "SW1") (pin "5") (pinfunction "RSPKR_5") (pintype "bidirectional"))
    )
    (net (code "13") (name "I2C_SCL") (class "Default")
      (node (ref "R15") (pin "1") (pinfunction "1_1") (pintype "passive"))
      (node (ref "R37") (pin "1") (pinfunction "1_1") (pintype "passive"))
      (node (ref "U1") (pin "112") (pinfunction "X1D26_112") (pintype "bidirectional"))
      (node (ref "U6") (pin "17") (pinfunction "SCLK_17") (pintype "bidirectional"))
    )
    (net (code "14") (name "I2C_SDA") (class "Default")
      (node (ref "R16") (pin "1") (pinfunction "1_1") (pintype "passive"))
      (node (ref "R36") (pin "1") (pinfunction "1_1") (pintype "passive"))
      (node (ref "U1") (pin "113") (pinfunction "X1D27_113") (pintype "bidirectional"))
      (node (ref "U6") (pin "18") (pinfunction "SDIN_18") (pintype "bidirectional"))
    )
    (net (code "15") (name "I2S_BCLK") (class "Default")
      (node (ref "R33") (pin "2") (pinfunction "2_2") (pintype "passive"))
      (node (ref "U1") (pin "15") (pinfunction "X1D36_15") (pintype "bidirectional"))
    )
    (net (code "16") (name "I2S_DAC_DATA") (class "Default")
      (node (ref "R41") (pin "2") (pinfunction "2_2") (pintype "passive"))
      (node (ref "U1") (pin "21") (pinfunction "X1D39_21") (pintype "bidirectional"))
    )
    (net (code "17") (name "I2S_LRCK") (class "Default")
      (node (ref "R40") (pin "2") (pinfunction "2_2") (pintype "passive"))
      (node (ref "U1") (pin "18") (pinfunction "X1D37_18") (pintype "bidirectional"))
    )
    (net (code "18") (name "LED_DATA") (class "Default")
      (node (ref "R44") (pin "1") (pinfunction "1_1") (pintype "passive"))
      (node (ref "SK0") (pin "3") (pinfunction "DIN_3") (pintype "bidirectional"))
    )
    (net (code "19") (name "LED_DATA_IN") (class "Default")
      (node (ref "C77") (pin "1") (pinfunction "1_1") (pintype "passive"))
      (node (ref "R45") (pin "2") (pinfunction "2_2") (pintype "passive"))
      (node (ref "R47") (pin "2") (pinfunction "2_2") (pintype "passive"))
      (node (ref "U13") (pin "2") (pinfunction "A_2") (pintype "bidirectional"))
    )
    (net (code "20") (name "MCLK") (class "Default")
      (node (ref "C85") (pin "2") (pinfunction "2_2") (pintype "passive"))
      (node (ref "R50") (pin "1") (pinfunction "1_1") (pintype "passive"))
      (node (ref "U1") (pin "63") (pinfunction "X0D13_63") (pintype "bidirectional"))
      (node (ref "U8") (pin "2") (pinfunction "CP_2") (pintype "bidirectional"))
    )
    (net (code "21") (name "MCLK_TILE1") (class "Default")
      (node (ref "C84") (pin "2") (pinfunction "2_2") (pintype "passive"))
      (node (ref "R49") (pin "1") (pinfunction "1_1") (pintype "passive"))
      (node (ref "U1") (pin "20") (pinfunction "X1D38_20") (pintype "bidirectional"))
    )
    (net (code "22") (name "MIC_CLK") (class "Default")
      (node (ref "C108") (pin "2") (pinfunction "2_2") (pintype "passive"))
      (node (ref "R42") (pin "1") (pinfunction "1_1") (pintype "passive"))
      (node (ref "R48") (pin "2") (pinfunction "2_2") (pintype "passive"))
      (node (ref "U8") (pin "1") (pinfunction "D_1") (pintype "bidirectional"))
    )
    (net (code "23") (name "MIC_CLK0") (class "Default")
      (node (ref "C101") (pin "2") (pinfunction "2_2") (pintype "passive"))
      (node (ref "MIC7") (pin "3") (pinfunction "CLK_3") (pintype "bidirectional"))
      (node (ref "MIC_CLK0") (pin "T") (pinfunction "T_T") (pintype "bidirectional"))
      (node (ref "R29") (pin "2") (pinfunction "2_2") (pintype "passive"))
    )
    (net (code "24") (name "MIC_CLK1") (class "Default")
      (node (ref "C94") (pin "2") (pinfunction "2_2") (pintype "passive"))
      (node (ref "MIC8") (pin "3") (pinfunction "CLK_3") (pintype "bidirectional"))
      (node (ref "MIC_CLK1") (pin "T") (pinfunction "T_T") (pintype "bidirectional"))
      (node (ref "R26") (pin "2") (pinfunction "2_2") (pintype "passive"))
    )
    (net (code "25") (name "MIC_CLK2") (class "Default")
      (node (ref "C87") (pin "2") (pinfunction "2_2") (pintype "passive"))
      (node (ref "MIC9") (pin "3") (pinfunction "CLK_3") (pintype "bidirectional"))
      (node (ref "MIC_CLK2") (pin "T") (pinfunction "T_T") (pintype "bidirectional"))
      (node (ref "R28") (pin "2") (pinfunction "2_2") (pintype "passive"))
    )
    (net (code "26") (name "MIC_CLK3") (class "Default")
      (node (ref "C104") (pin "2") (pinfunction "2_2") (pintype "passive"))
      (node (ref "MIC10") (pin "3") (pinfunction "CLK_3") (pintype "bidirectional"))
      (node (ref "MIC_CLK3") (pin "T") (pinfunction "T_T") (pintype "bidirectional"))
      (node (ref "R30") (pin "2") (pinfunction "2_2") (pintype "passive"))
    )
    (net (code "27") (name "MIC_CLK4") (class "Default")
      (node (ref "C103") (pin "2") (pinfunction "2_2") (pintype "passive"))
      (node (ref "MIC11") (pin "3") (pinfunction "CLK_3") (pintype "bidirectional"))
      (node (ref "MIC_CLK4") (pin "T") (pinfunction "T_T") (pintype "bidirectional"))
      (node (ref "R31") (pin "2") (pinfunction "2_2") (pintype "passive"))
    )
    (net (code "28") (name "MIC_CLK5") (class "Default")
      (node (ref "C106") (pin "2") (pinfunction "2_2") (pintype "passive"))
      (node (ref "MIC12") (pin "3") (pinfunction "CLK_3") (pintype "bidirectional"))
      (node (ref "MIC_CLK5") (pin "T") (pinfunction "T_T") (pintype "bidirectional"))
      (node (ref "R52") (pin "2") (pinfunction "2_2") (pintype "passive"))
    )
    (net (code "29") (name "MIC_CLK6") (class "Default")
      (node (ref "C105") (pin "2") (pinfunction "2_2") (pintype "passive"))
      (node (ref "MIC13") (pin "3") (pinfunction "CLK_3") (pintype "bidirectional"))
      (node (ref "MIC_CLK6") (pin "T") (pinfunction "T_T") (pintype "bidirectional"))
      (node (ref "R53") (pin "2") (pinfunction "2_2") (pintype "passive"))
    )
    (net (code "30") (name "MIC_DATA0") (class "Default")
      (node (ref "MIC7") (pin "4") (pinfunction "DOUT_4") (pintype "bidirectional"))
      (node (ref "R65") (pin "2") (pinfunction "2_2") (pintype "passive"))
    )
    (net (code "31") (name "MIC_DATA1") (class "Default")
      (node (ref "MIC8") (pin "4") (pinfunction "DOUT_4") (pintype "bidirectional"))
      (node (ref "R64") (pin "2") (pinfunction "2_2") (pintype "passive"))
    )
    (net (code "32") (name "MIC_DATA2") (class "Default")
      (node (ref "MIC9") (pin "4") (pinfunction "DOUT_4") (pintype "bidirectional"))
      (node (ref "R62") (pin "1") (pinfunction "1_1") (pintype "passive"))
    )
    (net (code "33") (name "MIC_DATA3") (class "Default")
      (node (ref "MIC10") (pin "4") (pinfunction "DOUT_4") (pintype "bidirectional"))
      (node (ref "R61") (pin "1") (pinfunction "1_1") (pintype "passive"))
    )
    (net (code "34") (name "MIC_DATA4") (class "Default")
      (node (ref "MIC11") (pin "4") (pinfunction "DOUT_4") (pintype "bidirectional"))
      (node (ref "R60") (pin "1") (pinfunction "1_1") (pintype "passive"))
    )
    (net (code "35") (name "MIC_DATA5") (class "Default")
      (node (ref "MIC12") (pin "4") (pinfunction "DOUT_4") (pintype "bidirectional"))
      (node (ref "R58") (pin "1") (pinfunction "1_1") (pintype "passive"))
    )
    (net (code "36") (name "MIC_DATA6") (class "Default")
      (node (ref "MIC13") (pin "4") (pinfunction "DOUT_4") (pintype "bidirectional"))
      (node (ref "R63") (pin "2") (pinfunction "2_2") (pintype "passive"))
    )
    (net (code "37") (name "Net-(C95-Pad2)") (class "Default")
      (node (ref "C95") (pin "2") (pinfunction "2_2") (pintype "passive"))
      (node (ref "C97") (pin "2") (pinfunction "2_2") (pintype "passive"))
      (node (ref "C98") (pin "2") (pinfunction "2_2") (pintype "passive"))
      (node (ref "J10") (pin "2") (pinfunction "2_2") (pintype "bidirectional"))
      (node (ref "L7") (pin "2") (pinfunction "2_2") (pintype "passive"))
    )
    (net (code "38") (name "Net-(C96-Pad2)") (class "Default")
      (node (ref "C96") (pin "2") (pinfunction "2_2") (pintype "passive"))
      (node (ref "C97") (pin "1") (pinfunction "1_1") (pintype "passive"))
      (node (ref "C99") (pin "2") (pinfunction "2_2") (pintype "passive"))
      (node (ref "J10") (pin "1") (pinfunction "1_1") (pintype "bidirectional"))
      (node (ref "L6") (pin "2") (pinfunction "2_2") (pintype "passive"))
    )
    (net (code "39") (name "Net-(D9-Pad+)") (class "Default")
      (node (ref "D9") (pin "+") (pinfunction "+_+") (pintype "passive"))
      (node (ref "R34") (pin "1") (pinfunction "1_1") (pintype "passive"))
    )
    (net (code "40") (name "Net-(D11-Pad+)") (class "Default")
      (node (ref "D11") (pin "+") (pinfunction "+_+") (pintype "passive"))
      (node (ref "R25") (pin "1") (pinfunction "1_1") (pintype "passive"))
    )
    (net (code "41") (name "Net-(J1-ID)") (class "Default")
      (node (ref "J1") (pin "4") (pinfunction "ID_4") (pintype "bidirectional"))
      (node (ref "R43") (pin "2") (pinfunction "2_2") (pintype "passive"))
    )
    (net (code "42") (name "Net-(J2-Pad1)") (class "Default")
      (node (ref "J2") (pin "1") (pinfunction "1_1") (pintype "bidirectional"))
      (node (ref "J5") (pin "2") (pinfunction "2_2") (pintype "bidirectional"))
    )
    (net (code "43") (name "Net-(J2-Pad2)") (class "Default")
      (node (ref "J2") (pin "2") (pinfunction "2_2") (pintype "bidirectional"))
      (node (ref "J5") (pin "1") (pinfunction "1_1") (pintype "bidirectional"))
    )
    (net (code "44") (name "Net-(J2-Pad3)") (class "Default")
      (node (ref "J2") (pin "3") (pinfunction "3_3") (pintype "bidirectional"))
      (node (ref "J5") (pin "4") (pinfunction "4_4") (pintype "bidirectional"))
    )
    (net (code "45") (name "Net-(J2-Pad4)") (class "Default")
      (node (ref "J2") (pin "4") (pinfunction "4_4") (pintype "bidirectional"))
      (node (ref "J5") (pin "3") (pinfunction "3_3") (pintype "bidirectional"))
    )
    (net (code "46") (name "Net-(J2-Pad5)") (class "Default")
      (node (ref "J2") (pin "5") (pinfunction "5_5") (pintype "bidirectional"))
      (node (ref "J5") (pin "6") (pinfunction "6_6") (pintype "bidirectional"))
    )
    (net (code "47") (name "Net-(J2-Pad6)") (class "Default")
      (node (ref "J2") (pin "6") (pinfunction "6_6") (pintype "bidirectional"))
      (node (ref "J5") (pin "5") (pinfunction "5_5") (pintype "bidirectional"))
    )
    (net (code "48") (name "Net-(J2-Pad7)") (class "Default")
      (node (ref "J2") (pin "7") (pinfunction "7_7") (pintype "bidirectional"))
      (node (ref "J5") (pin "8") (pinfunction "8_8") (pintype "bidirectional"))
    )
    (net (code "49") (name "Net-(J2-Pad8)") (class "Default")
      (node (ref "J2") (pin "8") (pinfunction "8_8") (pintype "bidirectional"))
      (node (ref "J5") (pin "7") (pinfunction "7_7") (pintype "bidirectional"))
    )
    (net (code "50") (name "Net-(J2-Pad9)") (class "Default")
      (node (ref "J2") (pin "9") (pinfunction "9_9") (pintype "bidirectional"))
      (node (ref "J5") (pin "10") (pinfunction "10_10") (pintype "bidirectional"))
    )
    (net (code "51") (name "Net-(J2-Pad10)") (class "Default")
      (node (ref "J2") (pin "10") (pinfunction "10_10") (pintype "bidirectional"))
      (node (ref "J5") (pin "9") (pinfunction "9_9") (pintype "bidirectional"))
    )
    (net (code "52") (name "Net-(J2-Pad11)") (class "Default")
      (node (ref "J2") (pin "11") (pinfunction "11_11") (pintype "bidirectional"))
      (node (ref "J5") (pin "12") (pinfunction "12_12") (pintype "bidirectional"))
    )
    (net (code "53") (name "Net-(J2-Pad12)") (class "Default")
      (node (ref "J2") (pin "12") (pinfunction "12_12") (pintype "bidirectional"))
      (node (ref "J5") (pin "11") (pinfunction "11_11") (pintype "bidirectional"))
    )
    (net (code "54") (name "Net-(J2-Pad14)") (class "Default")
      (node (ref "J2") (pin "14") (pinfunction "14_14") (pintype "bidirectional"))
      (node (ref "J5") (pin "13") (pinfunction "13_13") (pintype "bidirectional"))
    )
    (net (code "55") (name "Net-(J2-Pad16)") (class "Default")
      (node (ref "J2") (pin "16") (pinfunction "16_16") (pintype "bidirectional"))
      (node (ref "J5") (pin "15") (pinfunction "15_15") (pintype "bidirectional"))
    )
    (net (code "56") (name "Net-(J3-Pad3)") (class "Default")
      (node (ref "J3") (pin "3") (pinfunction "3_3") (pintype "bidirectional"))
      (node (ref "J6") (pin "4") (pinfunction "4_4") (pintype "bidirectional"))
    )
    (net (code "57") (name "Net-(J3-Pad5)") (class "Default")
      (node (ref "J3") (pin "5") (pinfunction "5_5") (pintype "bidirectional"))
      (node (ref "J6") (pin "6") (pinfunction "6_6") (pintype "bidirectional"))
    )
    (net (code "58") (name "Net-(J3-Pad6)") (class "Default")
      (node (ref "J3") (pin "6") (pinfunction "6_6") (pintype "bidirectional"))
      (node (ref "J6") (pin "5") (pinfunction "5_5") (pintype "bidirectional"))
    )
    (net (code "59") (name "Net-(J3-Pad9)") (class "Default")
      (node (ref "J3") (pin "9") (pinfunction "9_9") (pintype "bidirectional"))
      (node (ref "J6") (pin "10") (pinfunction "10_10") (pintype "bidirectional"))
    )
    (net (code "60") (name "Net-(J3-Pad10)") (class "Default")
      (node (ref "J3") (pin "10") (pinfunction "10_10") (pintype "bidirectional"))
      (node (ref "J6") (pin "9") (pinfunction "9_9") (pintype "bidirectional"))
    )
    (net (code "61") (name "Net-(J3-Pad11)") (class "Default")
      (node (ref "J3") (pin "11") (pinfunction "11_11") (pintype "bidirectional"))
      (node (ref "J6") (pin "12") (pinfunction "12_12") (pintype "bidirectional"))
    )
    (net (code "62") (name "Net-(J3-Pad12)") (class "Default")
      (node (ref "J3") (pin "12") (pinfunction "12_12") (pintype "bidirectional"))
      (node (ref "J6") (pin "11") (pinfunction "11_11") (pintype "bidirectional"))
    )
    (net (code "63") (name "Net-(J3-Pad13)") (class "Default")
      (node (ref "J3") (pin "13") (pinfunction "13_13") (pintype "bidirectional"))
      (node (ref "J6") (pin "14") (pinfunction "14_14") (pintype "bidirectional"))
    )
    (net (code "64") (name "Net-(J3-Pad16)") (class "Default")
      (node (ref "J3") (pin "16") (pinfunction "16_16") (pintype "bidirectional"))
      (node (ref "J6") (pin "15") (pinfunction "15_15") (pintype "bidirectional"))
    )
    (net (code "65") (name "Net-(J9-Pad3)") (class "Default")
      (node (ref "J9") (pin "3") (pinfunction "3_3") (pintype "bidirectional"))
      (node (ref "L3") (pin "2") (pinfunction "2_2") (pintype "passive"))
    )
    (net (code "66") (name "Net-(J9-Pad4)") (class "Default")
      (node (ref "J9") (pin "4") (pinfunction "4_4") (pintype "bidirectional"))
      (node (ref "L4") (pin "2") (pinfunction "2_2") (pintype "passive"))
    )
    (net (code "67") (name "Net-(Q1-D)") (class "Default")
      (node (ref "D11") (pin "-") (pinfunction "-_-") (pintype "passive"))
      (node (ref "Q1") (pin "3") (pinfunction "D_3") (pintype "passive"))
    )
    (net (code "68") (name "Net-(SK0-DOUT)") (class "Default")
      (node (ref "SK0") (pin "1") (pinfunction "DOUT_1") (pintype "bidirectional"))
      (node (ref "SK1") (pin "3") (pinfunction "DIN_3") (pintype "bidirectional"))
    )
    (net (code "69") (name "Net-(SK1-DOUT)") (class "Default")
      (node (ref "SK1") (pin "1") (pinfunction "DOUT_1") (pintype "bidirectional"))
      (node (ref "SK2") (pin "3") (pinfunction "DIN_3") (pintype "bidirectional"))
    )
    (net (code "70") (name "Net-(SK2-DOUT)") (class "Default")
      (node (ref "SK2") (pin "1") (pinfunction "DOUT_1") (pintype "bidirectional"))
      (node (ref "SK3") (pin "3") (pinfunction "DIN_3") (pintype "bidirectional"))
    )
    (net (code "71") (name "Net-(SK3-DOUT)") (class "Default")
      (node (ref "SK3") (pin "1") (pinfunction "DOUT_1") (pintype "bidirectional"))
      (node (ref "SK4") (pin "3") (pinfunction "DIN_3") (pintype "bidirectional"))
    )
    (net (code "72") (name "Net-(SK4-DOUT)") (class "Default")
      (node (ref "SK4") (pin "1") (pinfunction "DOUT_1") (pintype "bidirectional"))
      (node (ref "SK5") (pin "3") (pinfunction "DIN_3") (pintype "bidirectional"))
    )
    (net (code "73") (name "Net-(SK5-DOUT)") (class "Default")
      (node (ref "SK5") (pin "1") (pinfunction "DOUT_1") (pintype "bidirectional"))
      (node (ref "SK6") (pin "3") (pinfunction "DIN_3") (pintype "bidirectional"))
    )
    (net (code "74") (name "Net-(SK7-DOUT)") (class "Default")
      (node (ref "SK7") (pin "1") (pinfunction "DOUT_1") (pintype "bidirectional"))
      (node (ref "SK8") (pin "3") (pinfunction "DIN_3") (pintype "bidirectional"))
    )
    (net (code "75") (name "Net-(SK8-DOUT)") (class "Default")
      (node (ref "SK8") (pin "1") (pinfunction "DOUT_1") (pintype "bidirectional"))
      (node (ref "SK9") (pin "3") (pinfunction "DIN_3") (pintype "bidirectional"))
    )
    (net (code "76") (name "Net-(SK10-DIN)") (class "Default")
      (node (ref "SK10") (pin "3") (pinfunction "DIN_3") (pintype "bidirectional"))
      (node (ref "SK9") (pin "1") (pinfunction "DOUT_1") (pintype "bidirectional"))
    )
    (net (code "77") (name "Net-(SK10-DOUT)") (class "Default")
      (node (ref "SK10") (pin "1") (pinfunction "DOUT_1") (pintype "bidirectional"))
      (node (ref "SK11") (pin "3") (pinfunction "DIN_3") (pintype "bidirectional"))
    )
    (net (code "78") (name "Net-(SW1-C_EXT)") (class "Default")
      (node (ref "C81") (pin "2") (pinfunction "2_2") (pintype "passive"))
      (node (ref "SW1") (pin "2") (pinfunction "C_EXT_2") (pintype "bidirectional"))
    )
    (net (code "79") (name "Net-(SW1-L2)") (class "Default")
      (node (ref "C91") (pin "2") (pinfunction "2_2") (pintype "passive"))
      (node (ref "C92") (pin "2") (pinfunction "2_2") (pintype "passive"))
      (node (ref "R3") (pin "2") (pinfunction "2_2") (pintype "passive"))
      (node (ref "SW1") (pin "11") (pinfunction "L2_11") (pintype "bidirectional"))
    )
    (net (code "80") (name "Net-(SW1-R2)") (class "Default")
      (node (ref "C90") (pin "2") (pinfunction "2_2") (pintype "passive"))
      (node (ref "C93") (pin "2") (pinfunction "2_2") (pintype "passive"))
      (node (ref "R39") (pin "2") (pinfunction "2_2") (pintype "passive"))
      (node (ref "SW1") (pin "9") (pinfunction "R2_9") (pintype "bidirectional"))
    )
    (net (code "81") (name "Net-(U1-USB_RTUNE)") (class "Default")
      (node (ref "R6") (pin "2") (pinfunction "2_2") (pintype "passive"))
      (node (ref "U1") (pin "48") (pinfunction "USB_RTUNE_48") (pintype "bidirectional"))
    )
    (net (code "82") (name "Net-(U1-X0D00)") (class "Default")
      (node (ref "R47") (pin "1") (pinfunction "1_1") (pintype "passive"))
      (node (ref "U1") (pin "30") (pinfunction "X0D00_30") (pintype "bidirectional"))
    )
    (net (code "83") (name "Net-(U1-X0D01)") (class "Default")
      (node (ref "R17") (pin "1") (pinfunction "1_1") (pintype "passive"))
      (node (ref "U1") (pin "27") (pinfunction "X0D01_27") (pintype "bidirectional"))
    )
    (net (code "84") (name "Net-(U1-X0D12)") (class "Default")
      (node (ref "R48") (pin "1") (pinfunction "1_1") (pintype "passive"))
      (node (ref "U1") (pin "62") (pinfunction "X0D12_62") (pintype "bidirectional"))
    )
    (net (code "85") (name "Net-(U1-X0D14)") (class "Default")
      (node (ref "C113") (pin "2") (pinfunction "2_2") (pintype "passive"))
      (node (ref "R65") (pin "1") (pinfunction "1_1") (pintype "passive"))
      (node (ref "U1") (pin "57") (pinfunction "X0D14_57") (pintype "bidirectional"))
    )
    (net (code "86") (name "Net-(U1-X0D15)") (class "Default")
      (node (ref "C114") (pin "2") (pinfunction "2_2") (pintype "passive"))
      (node (ref "R64") (pin "1") (pinfunction "1_1") (pintype "passive"))
      (node (ref "U1") (pin "58") (pinfunction "X0D15_58") (pintype "bidirectional"))
    )
    (net (code "87") (name "Net-(U1-X0D16)") (class "Default")
      (node (ref "C112") (pin "2") (pinfunction "2_2") (pintype "passive"))
      (node (ref "R62") (pin "2") (pinfunction "2_2") (pintype "passive"))
      (node (ref "U1") (pin "68") (pinfunction "X0D16_68") (pintype "bidirectional"))
    )
    (net (code "88") (name "Net-(U1-X0D17)") (class "Default")
      (node (ref "C111") (pin "2") (pinfunction "2_2") (pintype "passive"))
      (node (ref "R61") (pin "2") (pinfunction "2_2") (pintype "passive"))
      (node (ref "U1") (pin "69") (pinfunction "X0D17_69") (pintype "bidirectional"))
    )
    (net (code "89") (name "Net-(U1-X0D18)") (class "Default")
      (node (ref "C110") (pin "2") (pinfunction "2_2") (pintype "passive"))
      (node (ref "R60") (pin "2") (pinfunction "2_2") (pintype "passive"))
      (node (ref "U1") (pin "70") (pinfunction "X0D18_70") (pintype "bidirectional"))
    )
    (net (code "90") (name "Net-(U1-X0D19)") (class "Default")
      (node (ref "C109") (pin "2") (pinfunction "2_2") (pintype "passive"))
      (node (ref "R58") (pin "2") (pinfunction "2_2") (pintype "passive"))
      (node (ref "U1") (pin "71") (pinfunction "X0D19_71") (pintype "bidirectional"))
    )
    (net (code "91") (name "Net-(U1-X0D20)") (class "Default")
      (node (ref "C115") (pin "2") (pinfunction "2_2") (pintype "passive"))
      (node (ref "R63") (pin "1") (pinfunction "1_1") (pintype "passive"))
      (node (ref "U1") (pin "59") (pinfunction "X0D20_59") (pintype "bidirectional"))
    )
    (net (code "92") (name "Net-(U1-X0D24)") (class "Default")
      (node (ref "R36") (pin "2") (pinfunction "2_2") (pintype "passive"))
      (node (ref "U1") (pin "88") (pinfunction "X0D24_88") (pintype "bidirectional"))
    )
    (net (code "93") (name "Net-(U1-X0D25)") (class "Default")
      (node (ref "R37") (pin "2") (pinfunction "2_2") (pintype "passive"))
      (node (ref "U1") (pin "89") (pinfunction "X0D25_89") (pintype "bidirectional"))
    )
    (net (code "94") (name "Net-(U1-X0D42)") (class "Default")
      (node (ref "R12") (pin "1") (pinfunction "1_1") (pintype "passive"))
      (node (ref "U1") (pin "10") (pinfunction "X0D42_10") (pintype "bidirectional"))
    )
    (net (code "95") (name "Net-(U1-X0D43)") (class "Default")
      (node (ref "R14") (pin "1") (pinfunction "1_1") (pintype "passive"))
      (node (ref "U1") (pin "12") (pinfunction "X0D43_12") (pintype "bidirectional"))
    )
    (net (code "96") (name "Net-(U2-FB)") (class "Default")
      (node (ref "R5") (pin "1") (pinfunction "1_1") (pintype "passive"))
      (node (ref "R7") (pin "2") (pinfunction "2_2") (pintype "passive"))
      (node (ref "U2") (pin "4") (pinfunction "FB_4") (pintype "bidirectional"))
    )
    (net (code "97") (name "Net-(U2-SW)") (class "Default")
      (node (ref "L1") (pin "1") (pinfunction "1_1") (pintype "passive"))
      (node (ref "U2") (pin "2") (pinfunction "SW_2") (pintype "bidirectional"))
    )
    (net (code "98") (name "Net-(U3-FB)") (class "Default")
      (node (ref "R10") (pin "1") (pinfunction "1_1") (pintype "passive"))
      (node (ref "R11") (pin "2") (pinfunction "2_2") (pintype "passive"))
      (node (ref "U3") (pin "4") (pinfunction "FB_4") (pintype "bidirectional"))
    )
    (net (code "99") (name "Net-(U3-SW)") (class "Default")
      (node (ref "L2") (pin "1") (pinfunction "1_1") (pintype "passive"))
      (node (ref "U3") (pin "2") (pinfunction "SW_2") (pintype "bidirectional"))
    )
    (net (code "100") (name "Net-(U5-CEXT)") (class "Default")
      (node (ref "C63") (pin "2") (pinfunction "2_2") (pintype "passive"))
      (node (ref "U5") (pin "5") (pinfunction "CEXT_5") (pintype "bidirectional"))
    )
    (net (code "101") (name "Net-(U5-VIN)") (class "Default")
      (node (ref "ADM_VIN") (pin "T") (pinfunction "T_T") (pintype "bidirectional"))
      (node (ref "R22") (pin "2") (pinfunction "2_2") (pintype "passive"))
      (node (ref "R23") (pin "1") (pinfunction "1_1") (pintype "passive"))
      (node (ref "U5") (pin "3") (pinfunction "VIN_3") (pintype "bidirectional"))
    )
    (net (code "102") (name "Net-(U6-ADCLRC{slash}GPIO1)") (class "Default")
      (node (ref "R18") (pin "1") (pinfunction "1_1") (pintype "passive"))
      (node (ref "U6") (pin "15") (pinfunction "ADCLRC/GPIO1_15") (pintype "bidirectional"))
    )
    (net (code "103") (name "Net-(U6-HP_L)") (class "Default")
      (node (ref "C91") (pin "1") (pinfunction "1_1") (pintype "passive"))
      (node (ref "U6") (pin "31") (pinfunction "HP_L_31") (pintype "bidirectional"))
    )
    (net (code "104") (name "Net-(U6-HP_R)") (class "Default")
      (node (ref "C90") (pin "1") (pinfunction "1_1") (pintype "passive"))
      (node (ref "U6") (pin "29") (pinfunction "HP_R_29") (pintype "bidirectional"))
    )
    (net (code "105") (name "Net-(U6-SPK_RN)") (class "Default")
      (node (ref "L7") (pin "1") (pinfunction "1_1") (pintype "passive"))
      (node (ref "U6") (pin "19") (pinfunction "SPK_RN_19") (pintype "bidirectional"))
    )
    (net (code "106") (name "Net-(U6-SPK_RP)") (class "Default")
      (node (ref "L6") (pin "1") (pinfunction "1_1") (pintype "passive"))
      (node (ref "U6") (pin "22") (pinfunction "SPK_RP_22") (pintype "bidirectional"))
    )
    (net (code "107") (name "Net-(U8-Q)") (class "Default")
      (node (ref "R42") (pin "2") (pinfunction "2_2") (pintype "passive"))
      (node (ref "R46") (pin "2") (pinfunction "2_2") (pintype "passive"))
      (node (ref "U8") (pin "4") (pinfunction "Q_4") (pintype "bidirectional"))
    )
    (net (code "108") (name "Net-(U9-1Y)") (class "Default")
      (node (ref "R29") (pin "1") (pinfunction "1_1") (pintype "passive"))
      (node (ref "U9") (pin "7") (pinfunction "1Y_7") (pintype "bidirectional"))
    )
    (net (code "109") (name "Net-(U9-2Y)") (class "Default")
      (node (ref "R26") (pin "1") (pinfunction "1_1") (pintype "passive"))
      (node (ref "U9") (pin "5") (pinfunction "2Y_5") (pintype "bidirectional"))
    )
    (net (code "110") (name "Net-(U9-3Y)") (class "Default")
      (node (ref "R28") (pin "1") (pinfunction "1_1") (pintype "passive"))
      (node (ref "U9") (pin "2") (pinfunction "3Y_2") (pintype "bidirectional"))
    )
    (net (code "111") (name "Net-(U10-1Y)") (class "Default")
      (node (ref "R30") (pin "1") (pinfunction "1_1") (pintype "passive"))
      (node (ref "U10") (pin "7") (pinfunction "1Y_7") (pintype "bidirectional"))
    )
    (net (code "112") (name "Net-(U10-2Y)") (class "Default")
      (node (ref "R31") (pin "1") (pinfunction "1_1") (pintype "passive"))
      (node (ref "U10") (pin "5") (pinfunction "2Y_5") (pintype "bidirectional"))
    )
    (net (code "113") (name "Net-(U11-1Y)") (class "Default")
      (node (ref "R52") (pin "1") (pinfunction "1_1") (pintype "passive"))
      (node (ref "U11") (pin "7") (pinfunction "1Y_7") (pintype "bidirectional"))
    )
    (net (code "114") (name "Net-(U11-2Y)") (class "Default")
      (node (ref "R53") (pin "1") (pinfunction "1_1") (pintype "passive"))
      (node (ref "U11") (pin "5") (pinfunction "2Y_5") (pintype "bidirectional"))
    )
    (net (code "115") (name "Net-(U12-1Y)") (class "Default")
      (node (ref "R50") (pin "2") (pinfunction "2_2") (pintype "passive"))
      (node (ref "U12") (pin "7") (pinfunction "1Y_7") (pintype "bidirectional"))
    )
    (net (code "116") (name "Net-(U12-3Y)") (class "Default")
      (node (ref "R49") (pin "2") (pinfunction "2_2") (pintype "passive"))
      (node (ref "U12") (pin "2") (pinfunction "3Y_2") (pintype "bidirectional"))
    )
    (net (code "117") (name "Net-(U13-B)") (class "Default")
      (node (ref "R35") (pin "1") (pinfunction "1_1") (pintype "passive"))
      (node (ref "U13") (pin "1") (pinfunction "B_1") (pintype "bidirectional"))
    )
    (net (code "118") (name "Net-(U13-Y)") (class "Default")
      (node (ref "R44") (pin "2") (pinfunction "2_2") (pintype "passive"))
      (node (ref "U13") (pin "4") (pinfunction "Y_4") (pintype "bidirectional"))
    )
    (net (code "119") (name "Net-(X1-OUT)") (class "Default")
      (node (ref "R1") (pin "1") (pinfunction "1_1") (pintype "passive"))
      (node (ref "X1") (pin "3") (pinfunction "OUT_3") (pintype "bidirectional"))
    )
    (net (code "120") (name "Net-(X2-OUT)") (class "Default")
      (node (ref "R19") (pin "1") (pinfunction "1_1") (pintype "passive"))
      (node (ref "X2") (pin "3") (pinfunction "OUT_3") (pintype "bidirectional"))
    )
    (net (code "121") (name "PG_3V3") (class "Default")
      (node (ref "PG") (pin "T") (pinfunction "T_T") (pintype "bidirectional"))
      (node (ref "R21") (pin "1") (pinfunction "1_1") (pintype "passive"))
      (node (ref "U3") (pin "5") (pinfunction "EN_5") (pintype "bidirectional"))
      (node (ref "U5") (pin "1") (pinfunction "ENIN/~{ENIN}_1") (pintype "bidirectional"))
    )
    (net (code "122") (name "PLL_AVDD") (class "Default")
      (node (ref "C23") (pin "2") (pinfunction "2_2") (pintype "passive"))
      (node (ref "R13") (pin "1") (pinfunction "1_1") (pintype "passive"))
      (node (ref "U1") (pin "103") (pinfunction "PLL_AVDD_103") (pintype "bidirectional"))
    )
    (net (code "123") (name "PLL_OUT") (class "Default")
      (node (ref "C78") (pin "2") (pinfunction "2_2") (pintype "passive"))
      (node (ref "R18") (pin "2") (pinfunction "2_2") (pintype "passive"))
      (node (ref "U12") (pin "1") (pinfunction "1A_1") (pintype "bidirectional"))
      (node (ref "U12") (pin "3") (pinfunction "2A_3") (pintype "bidirectional"))
      (node (ref "U12") (pin "6") (pinfunction "3A_6") (pintype "bidirectional"))
    )
    (net (code "124") (name "POR") (class "Default")
      (node (ref "POR") (pin "T") (pinfunction "T_T") (pintype "bidirectional"))
      (node (ref "Q1") (pin "1") (pinfunction "G_1") (pintype "passive"))
      (node (ref "R24") (pin "1") (pinfunction "1_1") (pintype "passive"))
      (node (ref "U4") (pin "2") (pinfunction "A_2") (pintype "bidirectional"))
      (node (ref "U5") (pin "4") (pinfunction "ENOUT/~{ENOUT}_4") (pintype "bidirectional"))
    )
    (net (code "125") (name "PRE_MIC_CLK") (class "Default")
      (node (ref "C86") (pin "2") (pinfunction "2_2") (pintype "passive"))
      (node (ref "PMCK") (pin "T") (pinfunction "T_T") (pintype "bidirectional"))
      (node (ref "R46") (pin "1") (pinfunction "1_1") (pintype "passive"))
      (node (ref "U10") (pin "1") (pinfunction "1A_1") (pintype "bidirectional"))
      (node (ref "U10") (pin "3") (pinfunction "2A_3") (pintype "bidirectional"))
      (node (ref "U10") (pin "6") (pinfunction "3A_6") (pintype "bidirectional"))
      (node (ref "U11") (pin "1") (pinfunction "1A_1") (pintype "bidirectional"))
      (node (ref "U11") (pin "3") (pinfunction "2A_3") (pintype "bidirectional"))
      (node (ref "U11") (pin "6") (pinfunction "3A_6") (pintype "bidirectional"))
      (node (ref "U9") (pin "1") (pinfunction "1A_1") (pintype "bidirectional"))
      (node (ref "U9") (pin "3") (pinfunction "2A_3") (pintype "bidirectional"))
      (node (ref "U9") (pin "6") (pinfunction "3A_6") (pintype "bidirectional"))
    )
    (net (code "126") (name "RST_N") (class "Default")
      (node (ref "C66") (pin "2") (pinfunction "2_2") (pintype "passive"))
      (node (ref "R27") (pin "1") (pinfunction "1_1") (pintype "passive"))
      (node (ref "RST") (pin "T") (pinfunction "T_T") (pintype "bidirectional"))
      (node (ref "U1") (pin "123") (pinfunction "TRST_N_123") (pintype "bidirectional"))
      (node (ref "U1") (pin "124") (pinfunction "RST_N_124") (pintype "bidirectional"))
      (node (ref "U4") (pin "4") (pinfunction "Y_4") (pintype "bidirectional"))
    )
    (net (code "127") (name "SYS_1V") (class "Default")
      (node (ref "1V") (pin "T") (pinfunction "T_T") (pintype "bidirectional"))
      (node (ref "C18") (pin "2") (pinfunction "2_2") (pintype "passive"))
      (node (ref "C20") (pin "2") (pinfunction "2_2") (pintype "passive"))
      (node (ref "C25") (pin "2") (pinfunction "2_2") (pintype "passive"))
      (node (ref "C26") (pin "2") (pinfunction "2_2") (pintype "passive"))
      (node (ref "C27") (pin "2") (pinfunction "2_2") (pintype "passive"))
      (node (ref "C28") (pin "2") (pinfunction "2_2") (pintype "passive"))
      (node (ref "C29") (pin "2") (pinfunction "2_2") (pintype "passive"))
      (node (ref "C30") (pin "2") (pinfunction "2_2") (pintype "passive"))
      (node (ref "C31") (pin "2") (pinfunction "2_2") (pintype "passive"))
      (node (ref "C32") (pin "2") (pinfunction "2_2") (pintype "passive"))
      (node (ref "C33") (pin "2") (pinfunction "2_2") (pintype "passive"))
      (node (ref "C34") (pin "2") (pinfunction "2_2") (pintype "passive"))
      (node (ref "C35") (pin "2") (pinfunction "2_2") (pintype "passive"))
      (node (ref "C36") (pin "2") (pinfunction "2_2") (pintype "passive"))
      (node (ref "C37") (pin "2") (pinfunction "2_2") (pintype "passive"))
      (node (ref "C38") (pin "2") (pinfunction "2_2") (pintype "passive"))
      (node (ref "L2") (pin "2") (pinfunction "2_2") (pintype "passive"))
      (node (ref "R10") (pin "2") (pinfunction "2_2") (pintype "passive"))
      (node (ref "R13") (pin "2") (pinfunction "2_2") (pintype "passive"))
      (node (ref "R23") (pin "2") (pinfunction "2_2") (pintype "passive"))
      (node (ref "U1") (pin "101") (pinfunction "VDD_101") (pintype "bidirectional"))
      (node (ref "U1") (pin "102") (pinfunction "VDD_102") (pintype "bidirectional"))
      (node (ref "U1") (pin "11") (pinfunction "VDD_11") (pintype "bidirectional"))
      (node (ref "U1") (pin "120") (pinfunction "VDD_120") (pintype "bidirectional"))
      (node (ref "U1") (pin "126") (pinfunction "VDD_126") (pintype "bidirectional"))
      (node (ref "U1") (pin "16") (pinfunction "VDD_16") (pintype "bidirectional"))
      (node (ref "U1") (pin "17") (pinfunction "VDD_17") (pintype "bidirectional"))
      (node (ref "U1") (pin "24") (pinfunction "VDD_24") (pintype "bidirectional"))
      (node (ref "U1") (pin "36") (pinfunction "VDD_36") (pintype "bidirectional"))
      (node (ref "U1") (pin "41") (pinfunction "VDD_41") (pintype "bidirectional"))
      (node (ref "U1") (pin "49") (pinfunction "USB_VDD_49") (pintype "bidirectional"))
      (node (ref "U1") (pin "56") (pinfunction "VDD_56") (pintype "bidirectional"))
      (node (ref "U1") (pin "60") (pinfunction "VDD_60") (pintype "bidirectional"))
      (node (ref "U1") (pin "73") (pinfunction "VDD_73") (pintype "bidirectional"))
      (node (ref "U1") (pin "80") (pinfunction "VDD_80") (pintype "bidirectional"))
      (node (ref "U1") (pin "81") (pinfunction "VDD_81") (pintype "bidirectional"))
      (node (ref "U1") (pin "87") (pinfunction "VDD_87") (pintype "bidirectional"))
    )
    (net (code "128") (name "SYS_3V3") (class "Default")
      (node (ref "3V3") (pin "T") (pinfunction "T_T") (pintype "bidirectional"))
      (node (ref "C1") (pin "2") (pinfunction "2_2") (pintype "passive"))
      (node (ref "C107") (pin "2") (pinfunction "2_2") (pintype "passive"))
      (node (ref "C2") (pin "2") (pinfunction "2_2") (pintype "passive"))
      (node (ref "C24") (pin "2") (pinfunction "2_2") (pintype "passive"))
      (node (ref "C39") (pin "2") (pinfunction "2_2") (pintype "passive"))
      (node (ref "C40") (pin "2") (pinfunction "2_2") (pintype "passive"))
      (node (ref "C41") (pin "2") (pinfunction "2_2") (pintype "passive"))
      (node (ref "C42") (pin "2") (pinfunction "2_2") (pintype "passive"))
      (node (ref "C43") (pin "2") (pinfunction "2_2") (pintype "passive"))
      (node (ref "C44") (pin "2") (pinfunction "2_2") (pintype "passive"))
      (node (ref "C45") (pin "2") (pinfunction "2_2") (pintype "passive"))
      (node (ref "C46") (pin "2") (pinfunction "2_2") (pintype "passive"))
      (node (ref "C47") (pin "2") (pinfunction "2_2") (pintype "passive"))
      (node (ref "C48") (pin "2") (pinfunction "2_2") (pintype "passive"))
      (node (ref "C49") (pin "2") (pinfunction "2_2") (pintype "passive"))
      (node (ref "C5") (pin "2") (pinfunction "2_2") (pintype "passive"))
      (node (ref "C50") (pin "2") (pinfunction "2_2") (pintype "passive"))
      (node (ref "C51") (pin "2") (pinfunction "2_2") (pintype "passive"))
      (node (ref "C52") (pin "2") (pinfunction "2_2") (pintype "passive"))
      (node (ref "C55") (pin "2") (pinfunction "2_2") (pintype "passive"))
      (node (ref "C56") (pin "2") (pinfunction "2_2") (pintype "passive"))
      (node (ref "C57") (pin "2") (pinfunction "2_2") (pintype "passive"))
      (node (ref "C58") (pin "2") (pinfunction "2_2") (pintype "passive"))
      (node (ref "C59") (pin "2") (pinfunction "2_2") (pintype "passive"))
      (node (ref "C60") (pin "2") (pinfunction "2_2") (pintype "passive"))
      (node (ref "C61") (pin "2") (pinfunction "2_2") (pintype "passive"))
      (node (ref "C64") (pin "2") (pinfunction "2_2") (pintype "passive"))
      (node (ref "C65") (pin "2") (pinfunction "2_2") (pintype "passive"))
      (node (ref "C67") (pin "2") (pinfunction "2_2") (pintype "passive"))
      (node (ref "C70") (pin "2") (pinfunction "2_2") (pintype "passive"))
      (node (ref "C8") (pin "2") (pinfunction "2_2") (pintype "passive"))
      (node (ref "C88") (pin "2") (pinfunction "2_2") (pintype "passive"))
      (node (ref "C9") (pin "2") (pinfunction "2_2") (pintype "passive"))
      (node (ref "L1") (pin "2") (pinfunction "2_2") (pintype "passive"))
      (node (ref "MIC10") (pin "1") (pinfunction "VDD_1") (pintype "bidirectional"))
      (node (ref "MIC11") (pin "1") (pinfunction "VDD_1") (pintype "bidirectional"))
      (node (ref "MIC12") (pin "1") (pinfunction "VDD_1") (pintype "bidirectional"))
      (node (ref "MIC13") (pin "1") (pinfunction "VDD_1") (pintype "bidirectional"))
      (node (ref "MIC7") (pin "1") (pinfunction "VDD_1") (pintype "bidirectional"))
      (node (ref "MIC8") (pin "1") (pinfunction "VDD_1") (pintype "bidirectional"))
      (node (ref "MIC9") (pin "1") (pinfunction "VDD_1") (pintype "bidirectional"))
      (node (ref "R15") (pin "2") (pinfunction "2_2") (pintype "passive"))
      (node (ref "R16") (pin "2") (pinfunction "2_2") (pintype "passive"))
      (node (ref "R17") (pin "2") (pinfunction "2_2") (pintype "passive"))
      (node (ref "R2") (pin "2") (pinfunction "2_2") (pintype "passive"))
      (node (ref "R21") (pin "2") (pinfunction "2_2") (pintype "passive"))
      (node (ref "R24") (pin "2") (pinfunction "2_2") (pintype "passive"))
      (node (ref "R25") (pin "2") (pinfunction "2_2") (pintype "passive"))
      (node (ref "R27") (pin "2") (pinfunction "2_2") (pintype "passive"))
      (node (ref "R5") (pin "2") (pinfunction "2_2") (pintype "passive"))
      (node (ref "U1") (pin "105") (pinfunction "OTP_VCC_105") (pintype "bidirectional"))
      (node (ref "U1") (pin "110") (pinfunction "VDDIOT_110") (pintype "bidirectional"))
      (node (ref "U1") (pin "111") (pinfunction "VDDIOT_111") (pintype "bidirectional"))
      (node (ref "U1") (pin "14") (pinfunction "VDDIOL_14") (pintype "bidirectional"))
      (node (ref "U1") (pin "19") (pinfunction "VDDIOL_19") (pintype "bidirectional"))
      (node (ref "U1") (pin "29") (pinfunction "VDDIOL_29") (pintype "bidirectional"))
      (node (ref "U1") (pin "42") (pinfunction "VDDIOL_42") (pintype "bidirectional"))
      (node (ref "U1") (pin "44") (pinfunction "USB_VDD33_44") (pintype "bidirectional"))
      (node (ref "U1") (pin "52") (pinfunction "VDDIOR_52") (pintype "bidirectional"))
      (node (ref "U1") (pin "6") (pinfunction "VDDIOL_6") (pintype "bidirectional"))
      (node (ref "U1") (pin "67") (pinfunction "VDDIOR_67") (pintype "bidirectional"))
      (node (ref "U1") (pin "78") (pinfunction "VDDIOR_78") (pintype "bidirectional"))
      (node (ref "U1") (pin "83") (pinfunction "VDDIOR_83") (pintype "bidirectional"))
      (node (ref "U1") (pin "92") (pinfunction "VDDIOR_92") (pintype "bidirectional"))
      (node (ref "U10") (pin "8") (pinfunction "VCC_8") (pintype "bidirectional"))
      (node (ref "U11") (pin "8") (pinfunction "VCC_8") (pintype "bidirectional"))
      (node (ref "U12") (pin "8") (pinfunction "VCC_8") (pintype "bidirectional"))
      (node (ref "U4") (pin "5") (pinfunction "VCC_5") (pintype "bidirectional"))
      (node (ref "U5") (pin "6") (pinfunction "VCC_6") (pintype "bidirectional"))
      (node (ref "U6") (pin "10") (pinfunction "DBVDD_10") (pintype "bidirectional"))
      (node (ref "U6") (pin "8") (pinfunction "DCVDD_8") (pintype "bidirectional"))
      (node (ref "U8") (pin "5") (pinfunction "VCC_5") (pintype "bidirectional"))
      (node (ref "U9") (pin "8") (pinfunction "VCC_8") (pintype "bidirectional"))
      (node (ref "X1") (pin "1") (pinfunction "ENABLE_1") (pintype "bidirectional"))
      (node (ref "X1") (pin "4") (pinfunction "VDD_4") (pintype "bidirectional"))
      (node (ref "X2") (pin "1") (pinfunction "ENABLE_1") (pintype "bidirectional"))
      (node (ref "X2") (pin "4") (pinfunction "VDD_4") (pintype "bidirectional"))
    )
    (net (code "129") (name "TCK") (class "Default")
      (node (ref "TCK") (pin "T") (pinfunction "T_T") (pintype "bidirectional"))
      (node (ref "U1") (pin "128") (pinfunction "TCK_128") (pintype "bidirectional"))
    )
    (net (code "130") (name "TDI") (class "Default")
      (node (ref "TDI") (pin "T") (pinfunction "T_T") (pintype "bidirectional"))
      (node (ref "U1") (pin "2") (pinfunction "TDI_2") (pintype "bidirectional"))
    )
    (net (code "131") (name "TDO") (class "Default")
      (node (ref "TDO") (pin "T") (pinfunction "T_T") (pintype "bidirectional"))
      (node (ref "U1") (pin "1") (pinfunction "TDO_1") (pintype "bidirectional"))
    )
    (net (code "132") (name "TMS") (class "Default")
      (node (ref "TMS") (pin "T") (pinfunction "T_T") (pintype "bidirectional"))
      (node (ref "U1") (pin "127") (pinfunction "TMS_127") (pintype "bidirectional"))
    )
    (net (code "133") (name "USBDM") (class "Default")
      (node (ref "J2") (pin "15") (pinfunction "15_15") (pintype "bidirectional"))
      (node (ref "J5") (pin "16") (pinfunction "16_16") (pintype "bidirectional"))
      (node (ref "R9") (pin "1") (pinfunction "1_1") (pintype "passive"))
    )
    (net (code "134") (name "USBDP") (class "Default")
      (node (ref "J2") (pin "13") (pinfunction "13_13") (pintype "bidirectional"))
      (node (ref "J5") (pin "14") (pinfunction "14_14") (pintype "bidirectional"))
      (node (ref "R8") (pin "1") (pinfunction "1_1") (pintype "passive"))
    )
    (net (code "135") (name "VDD_5V") (class "Default")
      (node (ref "C10") (pin "2") (pinfunction "2_2") (pintype "passive"))
      (node (ref "C100") (pin "1") (pinfunction "1_1") (pintype "passive"))
      (node (ref "C11") (pin "2") (pinfunction "2_2") (pintype "passive"))
      (node (ref "C12") (pin "2") (pinfunction "2_2") (pintype "passive"))
      (node (ref "C13") (pin "2") (pinfunction "2_2") (pintype "passive"))
      (node (ref "C14") (pin "2") (pinfunction "2_2") (pintype "passive"))
      (node (ref "C15") (pin "2") (pinfunction "2_2") (pintype "passive"))
      (node (ref "C16") (pin "2") (pinfunction "2_2") (pintype "passive"))
      (node (ref "C17") (pin "2") (pinfunction "2_2") (pintype "passive"))
      (node (ref "C19") (pin "2") (pinfunction "2_2") (pintype "passive"))
      (node (ref "C21") (pin "2") (pinfunction "2_2") (pintype "passive"))
      (node (ref "C22") (pin "2") (pinfunction "2_2") (pintype "passive"))
      (node (ref "C3") (pin "2") (pinfunction "2_2") (pintype "passive"))
      (node (ref "C53") (pin "2") (pinfunction "2_2") (pintype "passive"))
      (node (ref "C54") (pin "2") (pinfunction "2_2") (pintype "passive"))
      (node (ref "C6") (pin "2") (pinfunction "2_2") (pintype "passive"))
      (node (ref "C62") (pin "2") (pinfunction "2_2") (pintype "passive"))
      (node (ref "C69") (pin "2") (pinfunction "2_2") (pintype "passive"))
      (node (ref "C7") (pin "2") (pinfunction "2_2") (pintype "passive"))
      (node (ref "C72") (pin "2") (pinfunction "2_2") (pintype "passive"))
      (node (ref "C73") (pin "2") (pinfunction "2_2") (pintype "passive"))
      (node (ref "C74") (pin "2") (pinfunction "2_2") (pintype "passive"))
      (node (ref "C75") (pin "2") (pinfunction "2_2") (pintype "passive"))
      (node (ref "C76") (pin "2") (pinfunction "2_2") (pintype "passive"))
      (node (ref "GND1") (pin "T") (pinfunction "T_T") (pintype "bidirectional"))
      (node (ref "J1") (pin "1") (pinfunction "VCC_1") (pintype "bidirectional"))
      (node (ref "J3") (pin "2") (pinfunction "2_2") (pintype "bidirectional"))
      (node (ref "J6") (pin "1") (pinfunction "1_1") (pintype "bidirectional"))
      (node (ref "R35") (pin "2") (pinfunction "2_2") (pintype "passive"))
      (node (ref "R43") (pin "1") (pinfunction "1_1") (pintype "passive"))
      (node (ref "SK0") (pin "4") (pinfunction "VDD_4") (pintype "bidirectional"))
      (node (ref "SK1") (pin "4") (pinfunction "VDD_4") (pintype "bidirectional"))
      (node (ref "SK10") (pin "4") (pinfunction "VDD_4") (pintype "bidirectional"))
      (node (ref "SK11") (pin "4") (pinfunction "VDD_4") (pintype "bidirectional"))
      (node (ref "SK2") (pin "4") (pinfunction "VDD_4") (pintype "bidirectional"))
      (node (ref "SK3") (pin "4") (pinfunction "VDD_4") (pintype "bidirectional"))
      (node (ref "SK4") (pin "4") (pinfunction "VDD_4") (pintype "bidirectional"))
      (node (ref "SK5") (pin "4") (pinfunction "VDD_4") (pintype "bidirectional"))
      (node (ref "SK6") (pin "4") (pinfunction "VDD_4") (pintype "bidirectional"))
      (node (ref "SK7") (pin "4") (pinfunction "VDD_4") (pintype "bidirectional"))
      (node (ref "SK8") (pin "4") (pinfunction "VDD_4") (pintype "bidirectional"))
      (node (ref "SK9") (pin "4") (pinfunction "VDD_4") (pintype "bidirectional"))
      (node (ref "U1") (pin "45") (pinfunction "USB_VBUS_45") (pintype "bidirectional"))
      (node (ref "U13") (pin "5") (pinfunction "VCC_5") (pintype "bidirectional"))
      (node (ref "U2") (pin "5") (pinfunction "EN_5") (pintype "bidirectional"))
      (node (ref "U2") (pin "7") (pinfunction "AVIN_7") (pintype "bidirectional"))
      (node (ref "U2") (pin "8") (pinfunction "PVIN_8") (pintype "bidirectional"))
      (node (ref "U3") (pin "7") (pinfunction "AVIN_7") (pintype "bidirectional"))
      (node (ref "U3") (pin "8") (pinfunction "PVIN_8") (pintype "bidirectional"))
      (node (ref "U6") (pin "21") (pinfunction "SPKVDD2_21") (pintype "bidirectional"))
      (node (ref "U6") (pin "26") (pinfunction "SPKVDD1_26") (pintype "bidirectional"))
      (node (ref "U7") (pin "3") (pinfunction "VIN_3") (pintype "bidirectional"))
    )
    (net (code "136") (name "VMID") (class "Default")
      (node (ref "C102") (pin "1") (pinfunction "1_1") (pintype "passive"))
      (node (ref "C4") (pin "2") (pinfunction "2_2") (pintype "passive"))
      (node (ref "TP14") (pin "T") (pinfunction "T_T") (pintype "bidirectional"))
      (node (ref "U6") (pin "27") (pinfunction "VMID_27") (pintype "bidirectional"))
    )
    (net (code "137") (name "XL_DN0") (class "Default")
      (node (ref "U1") (pin "9") (pinfunction "X0D41_9") (pintype "bidirectional"))
      (node (ref "XL_DN0") (pin "T") (pinfunction "T_T") (pintype "bidirectional"))
    )
    (net (code "138") (name "XL_DN1") (class "Default")
      (node (ref "U1") (pin "8") (pinfunction "X0D40_8") (pintype "bidirectional"))
      (node (ref "XL_DN1") (pin "T") (pinfunction "T_T") (pintype "bidirectional"))
    )
    (net (code "139") (name "XL_UP0") (class "Default")
      (node (ref "R12") (pin "2") (pinfunction "2_2") (pintype "passive"))
      (node (ref "XL_UP0") (pin "T") (pinfunction "T_T") (pintype "bidirectional"))
    )
    (net (code "140") (name "XL_UP1") (class "Default")
      (node (ref "R14") (pin "2") (pinfunction "2_2") (pintype "passive"))
      (node (ref "XL_UP1") (pin "T") (pinfunction "T_T") (pintype "bidirectional"))
    )
    (net (code "141") (name "XSYS_RST_N") (class "Default")
      (node (ref "J7") (pin "1") (pinfunction "1_1") (pintype "bidirectional"))
      (node (ref "R2") (pin "1") (pinfunction "1_1") (pintype "passive"))
      (node (ref "RST_N") (pin "T") (pinfunction "T_T") (pintype "bidirectional"))
      (node (ref "U4") (pin "1") (pinfunction "B_1") (pintype "bidirectional"))
    )
    (net (code "142") (name "XUSBDM_N") (class "Default")
      (node (ref "R38") (pin "1") (pinfunction "1_1") (pintype "passive"))
      (node (ref "R9") (pin "2") (pinfunction "2_2") (pintype "passive"))
      (node (ref "U1") (pin "47") (pinfunction "USB_DM_47") (pintype "bidirectional"))
    )
    (net (code "143") (name "XUSBDP_P") (class "Default")
      (node (ref "R4") (pin "1") (pinfunction "1_1") (pintype "passive"))
      (node (ref "R8") (pin "2") (pinfunction "2_2") (pintype "passive"))
      (node (ref "U1") (pin "46") (pinfunction "USB_DP_46") (pintype "bidirectional"))
    )
    (net (code "144") (name "_I2S_BCLK") (class "Default")
      (node (ref "C83") (pin "1") (pinfunction "1_1") (pintype "passive"))
      (node (ref "R33") (pin "1") (pinfunction "1_1") (pintype "passive"))
      (node (ref "U6") (pin "12") (pinfunction "BCLK_12") (pintype "bidirectional"))
    )
    (net (code "145") (name "_I2S_DAC_DATA") (class "Default")
      (node (ref "C80") (pin "1") (pinfunction "1_1") (pintype "passive"))
      (node (ref "R41") (pin "1") (pinfunction "1_1") (pintype "passive"))
      (node (ref "U6") (pin "14") (pinfunction "DACDAT_14") (pintype "bidirectional"))
    )
    (net (code "146") (name "_I2S_LRCK") (class "Default")
      (node (ref "C82") (pin "1") (pinfunction "1_1") (pintype "passive"))
      (node (ref "R40") (pin "1") (pinfunction "1_1") (pintype "passive"))
      (node (ref "U6") (pin "13") (pinfunction "DACLRC_13") (pintype "bidirectional"))
    )
    (net (code "147") (name "unconnected-(J9-Pad7)") (class "Default")
      (node (ref "J9") (pin "7") (pinfunction "7_7") (pintype "bidirectional"))
    )
    (net (code "148") (name "unconnected-(J9-Pad8)") (class "Default")
      (node (ref "J9") (pin "8") (pinfunction "8_8") (pintype "bidirectional"))
    )
    (net (code "149") (name "unconnected-(SK11-DOUT-Pad1)") (class "Default")
      (node (ref "SK11") (pin "1") (pinfunction "DOUT_1") (pintype "bidirectional"))
    )
    (net (code "150") (name "unconnected-(SW1-L1-Pad12)") (class "Default")
      (node (ref "SW1") (pin "12") (pinfunction "L1_12") (pintype "bidirectional"))
    )
    (net (code "151") (name "unconnected-(SW1-R1-Pad10)") (class "Default")
      (node (ref "SW1") (pin "10") (pinfunction "R1_10") (pintype "bidirectional"))
    )
    (net (code "152") (name "unconnected-(U1-NC-Pad50)") (class "Default")
      (node (ref "U1") (pin "50") (pinfunction "NC_50") (pintype "bidirectional"))
    )
    (net (code "153") (name "unconnected-(U1-NC-Pad65)") (class "Default")
      (node (ref "U1") (pin "65") (pinfunction "NC_65") (pintype "bidirectional"))
    )
    (net (code "154") (name "unconnected-(U1-USB_ID-Pad43)") (class "Default")
      (node (ref "U1") (pin "43") (pinfunction "USB_ID_43") (pintype "bidirectional"))
    )
    (net (code "155") (name "unconnected-(U1-X0D02-Pad37)") (class "Default")
      (node (ref "U1") (pin "37") (pinfunction "X0D02_37") (pintype "bidirectional"))
    )
    (net (code "156") (name "unconnected-(U1-X0D03-Pad38)") (class "Default")
      (node (ref "U1") (pin "38") (pinfunction "X0D03_38") (pintype "bidirectional"))
    )
    (net (code "157") (name "unconnected-(U1-X0D04-Pad31)") (class "Default")
      (node (ref "U1") (pin "31") (pinfunction "X0D04_31") (pintype "bidirectional"))
    )
    (net (code "158") (name "unconnected-(U1-X0D05-Pad33)") (class "Default")
      (node (ref "U1") (pin "33") (pinfunction "X0D05_33") (pintype "bidirectional"))
    )
    (net (code "159") (name "unconnected-(U1-X0D06-Pad34)") (class "Default")
      (node (ref "U1") (pin "34") (pinfunction "X0D06_34") (pintype "bidirectional"))
    )
    (net (code "160") (name "unconnected-(U1-X0D07-Pad35)") (class "Default")
      (node (ref "U1") (pin "35") (pinfunction "X0D07_35") (pintype "bidirectional"))
    )
    (net (code "161") (name "unconnected-(U1-X0D08-Pad39)") (class "Default")
      (node (ref "U1") (pin "39") (pinfunction "X0D08_39") (pintype "bidirectional"))
    )
    (net (code "162") (name "unconnected-(U1-X0D09-Pad40)") (class "Default")
      (node (ref "U1") (pin "40") (pinfunction "X0D09_40") (pintype "bidirectional"))
    )
    (net (code "163") (name "unconnected-(U1-X0D10-Pad28)") (class "Default")
      (node (ref "U1") (pin "28") (pinfunction "X0D10_28") (pintype "bidirectional"))
    )
    (net (code "164") (name "unconnected-(U1-X0D21-Pad61)") (class "Default")
      (node (ref "U1") (pin "61") (pinfunction "X0D21_61") (pintype "bidirectional"))
    )
    (net (code "165") (name "unconnected-(U1-X0D22-Pad64)") (class "Default")
      (node (ref "U1") (pin "64") (pinfunction "X0D22_64") (pintype "bidirectional"))
    )
    (net (code "166") (name "unconnected-(U1-X0D23-Pad66)") (class "Default")
      (node (ref "U1") (pin "66") (pinfunction "X0D23_66") (pintype "bidirectional"))
    )
    (net (code "167") (name "unconnected-(U1-X0D26-Pad93)") (class "Default")
      (node (ref "U1") (pin "93") (pinfunction "X0D26_93") (pintype "bidirectional"))
    )
    (net (code "168") (name "unconnected-(U1-X0D27-Pad94)") (class "Default")
      (node (ref "U1") (pin "94") (pinfunction "X0D27_94") (pintype "bidirectional"))
    )
    (net (code "169") (name "unconnected-(U1-X0D28-Pad96)") (class "Default")
      (node (ref "U1") (pin "96") (pinfunction "X0D28_96") (pintype "bidirectional"))
    )
    (net (code "170") (name "unconnected-(U1-X0D29-Pad98)") (class "Default")
      (node (ref "U1") (pin "98") (pinfunction "X0D29_98") (pintype "bidirectional"))
    )
    (net (code "171") (name "unconnected-(U1-X0D30-Pad99)") (class "Default")
      (node (ref "U1") (pin "99") (pinfunction "X0D30_99") (pintype "bidirectional"))
    )
    (net (code "172") (name "unconnected-(U1-X0D31-Pad100)") (class "Default")
      (node (ref "U1") (pin "100") (pinfunction "X0D31_100") (pintype "bidirectional"))
    )
    (net (code "173") (name "unconnected-(U1-X0D32-Pad95)") (class "Default")
      (node (ref "U1") (pin "95") (pinfunction "X0D32_95") (pintype "bidirectional"))
    )
    (net (code "174") (name "unconnected-(U1-X0D33-Pad97)") (class "Default")
      (node (ref "U1") (pin "97") (pinfunction "X0D33_97") (pintype "bidirectional"))
    )
    (net (code "175") (name "unconnected-(U1-X0D34-Pad90)") (class "Default")
      (node (ref "U1") (pin "90") (pinfunction "X0D34_90") (pintype "bidirectional"))
    )
    (net (code "176") (name "unconnected-(U1-X0D35-Pad91)") (class "Default")
      (node (ref "U1") (pin "91") (pinfunction "X0D35_91") (pintype "bidirectional"))
    )
    (net (code "177") (name "unconnected-(U1-X0D36-Pad3)") (class "Default")
      (node (ref "U1") (pin "3") (pinfunction "X0D36_3") (pintype "bidirectional"))
    )
    (net (code "178") (name "unconnected-(U1-X0D37-Pad4)") (class "Default")
      (node (ref "U1") (pin "4") (pinfunction "X0D37_4") (pintype "bidirectional"))
    )
    (net (code "179") (name "unconnected-(U1-X0D38-Pad5)") (class "Default")
      (node (ref "U1") (pin "5") (pinfunction "X0D38_5") (pintype "bidirectional"))
    )
    (net (code "180") (name "unconnected-(U1-X0D39-Pad7)") (class "Default")
      (node (ref "U1") (pin "7") (pinfunction "X0D39_7") (pintype "bidirectional"))
    )
    (net (code "181") (name "unconnected-(U1-X1D00-Pad85)") (class "Default")
      (node (ref "U1") (pin "85") (pinfunction "X1D00_85") (pintype "bidirectional"))
    )
    (net (code "182") (name "unconnected-(U1-X1D01-Pad86)") (class "Default")
      (node (ref "U1") (pin "86") (pinfunction "X1D01_86") (pintype "bidirectional"))
    )
    (net (code "183") (name "unconnected-(U1-X1D02-Pad72)") (class "Default")
      (node (ref "U1") (pin "72") (pinfunction "X1D02_72") (pintype "bidirectional"))
    )
    (net (code "184") (name "unconnected-(U1-X1D03-Pad74)") (class "Default")
      (node (ref "U1") (pin "74") (pinfunction "X1D03_74") (pintype "bidirectional"))
    )
    (net (code "185") (name "unconnected-(U1-X1D04-Pad75)") (class "Default")
      (node (ref "U1") (pin "75") (pinfunction "X1D04_75") (pintype "bidirectional"))
    )
    (net (code "186") (name "unconnected-(U1-X1D05-Pad76)") (class "Default")
      (node (ref "U1") (pin "76") (pinfunction "X1D05_76") (pintype "bidirectional"))
    )
    (net (code "187") (name "unconnected-(U1-X1D06-Pad77)") (class "Default")
      (node (ref "U1") (pin "77") (pinfunction "X1D06_77") (pintype "bidirectional"))
    )
    (net (code "188") (name "unconnected-(U1-X1D07-Pad79)") (class "Default")
      (node (ref "U1") (pin "79") (pinfunction "X1D07_79") (pintype "bidirectional"))
    )
    (net (code "189") (name "unconnected-(U1-X1D08-Pad82)") (class "Default")
      (node (ref "U1") (pin "82") (pinfunction "X1D08_82") (pintype "bidirectional"))
    )
    (net (code "190") (name "unconnected-(U1-X1D09-Pad84)") (class "Default")
      (node (ref "U1") (pin "84") (pinfunction "X1D09_84") (pintype "bidirectional"))
    )
    (net (code "191") (name "unconnected-(U1-X1D10-Pad121)") (class "Default")
      (node (ref "U1") (pin "121") (pinfunction "X1D10_121") (pintype "bidirectional"))
    )
    (net (code "192") (name "unconnected-(U1-X1D11-Pad122)") (class "Default")
      (node (ref "U1") (pin "122") (pinfunction "X1D11_122") (pintype "bidirectional"))
    )
    (net (code "193") (name "unconnected-(U1-X1D14-Pad51)") (class "Default")
      (node (ref "U1") (pin "51") (pinfunction "X1D14_51") (pintype "bidirectional"))
    )
    (net (code "194") (name "unconnected-(U1-X1D15-Pad53)") (class "Default")
      (node (ref "U1") (pin "53") (pinfunction "X1D15_53") (pintype "bidirectional"))
    )
    (net (code "195") (name "unconnected-(U1-X1D16-Pad22)") (class "Default")
      (node (ref "U1") (pin "22") (pinfunction "X1D16_22") (pintype "bidirectional"))
    )
    (net (code "196") (name "unconnected-(U1-X1D17-Pad23)") (class "Default")
      (node (ref "U1") (pin "23") (pinfunction "X1D17_23") (pintype "bidirectional"))
    )
    (net (code "197") (name "unconnected-(U1-X1D18-Pad25)") (class "Default")
      (node (ref "U1") (pin "25") (pinfunction "X1D18_25") (pintype "bidirectional"))
    )
    (net (code "198") (name "unconnected-(U1-X1D19-Pad26)") (class "Default")
      (node (ref "U1") (pin "26") (pinfunction "X1D19_26") (pintype "bidirectional"))
    )
    (net (code "199") (name "unconnected-(U1-X1D20-Pad54)") (class "Default")
      (node (ref "U1") (pin "54") (pinfunction "X1D20_54") (pintype "bidirectional"))
    )
    (net (code "200") (name "unconnected-(U1-X1D21-Pad55)") (class "Default")
      (node (ref "U1") (pin "55") (pinfunction "X1D21_55") (pintype "bidirectional"))
    )
    (net (code "201") (name "unconnected-(U1-X1D28-Pad114)") (class "Default")
      (node (ref "U1") (pin "114") (pinfunction "X1D28_114") (pintype "bidirectional"))
    )
    (net (code "202") (name "unconnected-(U1-X1D29-Pad115)") (class "Default")
      (node (ref "U1") (pin "115") (pinfunction "X1D29_115") (pintype "bidirectional"))
    )
    (net (code "203") (name "unconnected-(U1-X1D30-Pad116)") (class "Default")
      (node (ref "U1") (pin "116") (pinfunction "X1D30_116") (pintype "bidirectional"))
    )
    (net (code "204") (name "unconnected-(U1-X1D31-Pad117)") (class "Default")
      (node (ref "U1") (pin "117") (pinfunction "X1D31_117") (pintype "bidirectional"))
    )
    (net (code "205") (name "unconnected-(U1-X1D32-Pad118)") (class "Default")
      (node (ref "U1") (pin "118") (pinfunction "X1D32_118") (pintype "bidirectional"))
    )
    (net (code "206") (name "unconnected-(U1-X1D33-Pad119)") (class "Default")
      (node (ref "U1") (pin "119") (pinfunction "X1D33_119") (pintype "bidirectional"))
    )
    (net (code "207") (name "unconnected-(U1-X1D35-Pad13)") (class "Default")
      (node (ref "U1") (pin "13") (pinfunction "X1D35_13") (pintype "bidirectional"))
    )
    (net (code "208") (name "unconnected-(U1-X1D40-Pad106)") (class "Default")
      (node (ref "U1") (pin "106") (pinfunction "X1D40_106") (pintype "bidirectional"))
    )
    (net (code "209") (name "unconnected-(U1-X1D41-Pad107)") (class "Default")
      (node (ref "U1") (pin "107") (pinfunction "X1D41_107") (pintype "bidirectional"))
    )
    (net (code "210") (name "unconnected-(U1-X1D42-Pad108)") (class "Default")
      (node (ref "U1") (pin "108") (pinfunction "X1D42_108") (pintype "bidirectional"))
    )
    (net (code "211") (name "unconnected-(U1-X1D43-Pad109)") (class "Default")
      (node (ref "U1") (pin "109") (pinfunction "X1D43_109") (pintype "bidirectional"))
    )
    (net (code "212") (name "unconnected-(U6-ADCDAT-Pad16)") (class "Default")
      (node (ref "U6") (pin "16") (pinfunction "ADCDAT_16") (pintype "bidirectional"))
    )
    (net (code "213") (name "unconnected-(U6-LINPUT1-Pad4)") (class "Default")
      (node (ref "U6") (pin "4") (pinfunction "LINPUT1_4") (pintype "bidirectional"))
    )
    (net (code "214") (name "unconnected-(U6-LINPUT2-Pad3)") (class "Default")
      (node (ref "U6") (pin "3") (pinfunction "LINPUT2_3") (pintype "bidirectional"))
    )
    (net (code "215") (name "unconnected-(U6-LINPUT3{slash}JD2-Pad2)") (class "Default")
      (node (ref "U6") (pin "2") (pinfunction "LINPUT3/JD2_2") (pintype "bidirectional"))
    )
    (net (code "216") (name "unconnected-(U6-MICBIAS-Pad1)") (class "Default")
      (node (ref "U6") (pin "1") (pinfunction "MICBIAS_1") (pintype "bidirectional"))
    )
    (net (code "217") (name "unconnected-(U6-OUT3-Pad30)") (class "Default")
      (node (ref "U6") (pin "30") (pinfunction "OUT3_30") (pintype "bidirectional"))
    )
    (net (code "218") (name "unconnected-(U6-RINPUT1-Pad5)") (class "Default")
      (node (ref "U6") (pin "5") (pinfunction "RINPUT1_5") (pintype "bidirectional"))
    )
    (net (code "219") (name "unconnected-(U6-RINPUT2-Pad6)") (class "Default")
      (node (ref "U6") (pin "6") (pinfunction "RINPUT2_6") (pintype "bidirectional"))
    )
    (net (code "220") (name "unconnected-(U6-RINPUT3{slash}JD3-Pad7)") (class "Default")
      (node (ref "U6") (pin "7") (pinfunction "RINPUT3/JD3_7") (pintype "bidirectional"))
    )
    (net (code "221") (name "unconnected-(U6-SPK_LN-Pad23)") (class "Default")
      (node (ref "U6") (pin "23") (pinfunction "SPK_LN_23") (pintype "bidirectional"))
    )
    (net (code "222") (name "unconnected-(U6-SPK_LP-Pad25)") (class "Default")
      (node (ref "U6") (pin "25") (pinfunction "SPK_LP_25") (pintype "bidirectional"))
    )
    (net (code "223") (name "unconnected-(U10-3Y-Pad2)") (class "Default")
      (node (ref "U10") (pin "2") (pinfunction "3Y_2") (pintype "bidirectional"))
    )
    (net (code "224") (name "unconnected-(U11-3Y-Pad2)") (class "Default")
      (node (ref "U11") (pin "2") (pinfunction "3Y_2") (pintype "bidirectional"))
    )
    (net (code "225") (name "unconnected-(U12-2Y-Pad5)") (class "Default")
      (node (ref "U12") (pin "5") (pinfunction "2Y_5") (pintype "bidirectional"))
    )
  )
)
